# EEZ_DIB_MCU_r2B1.net
KiCad netlist of a schematic drawn in EAGLE
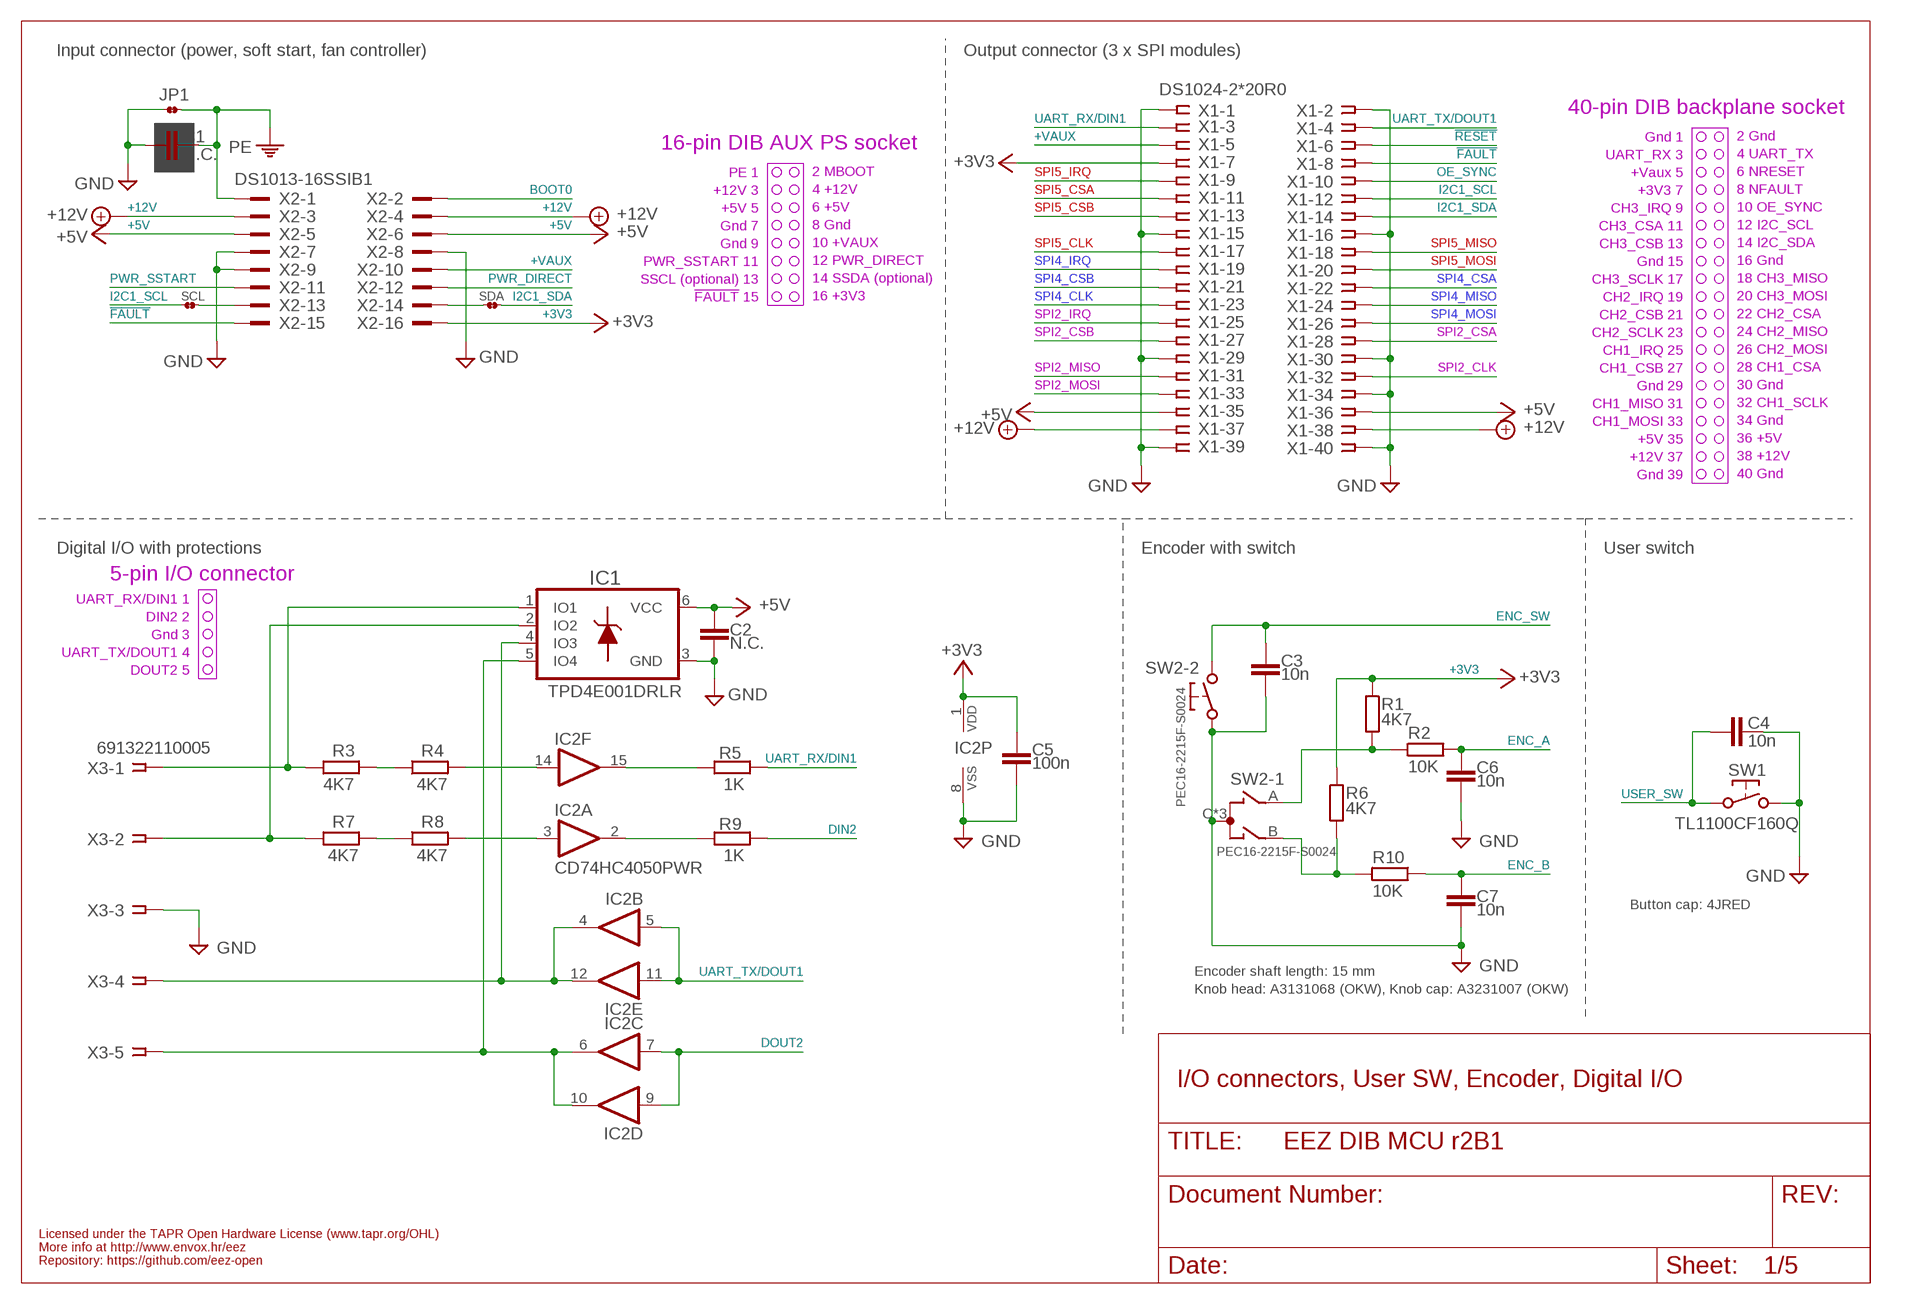
[diagram p0: schematic, sheet 1]
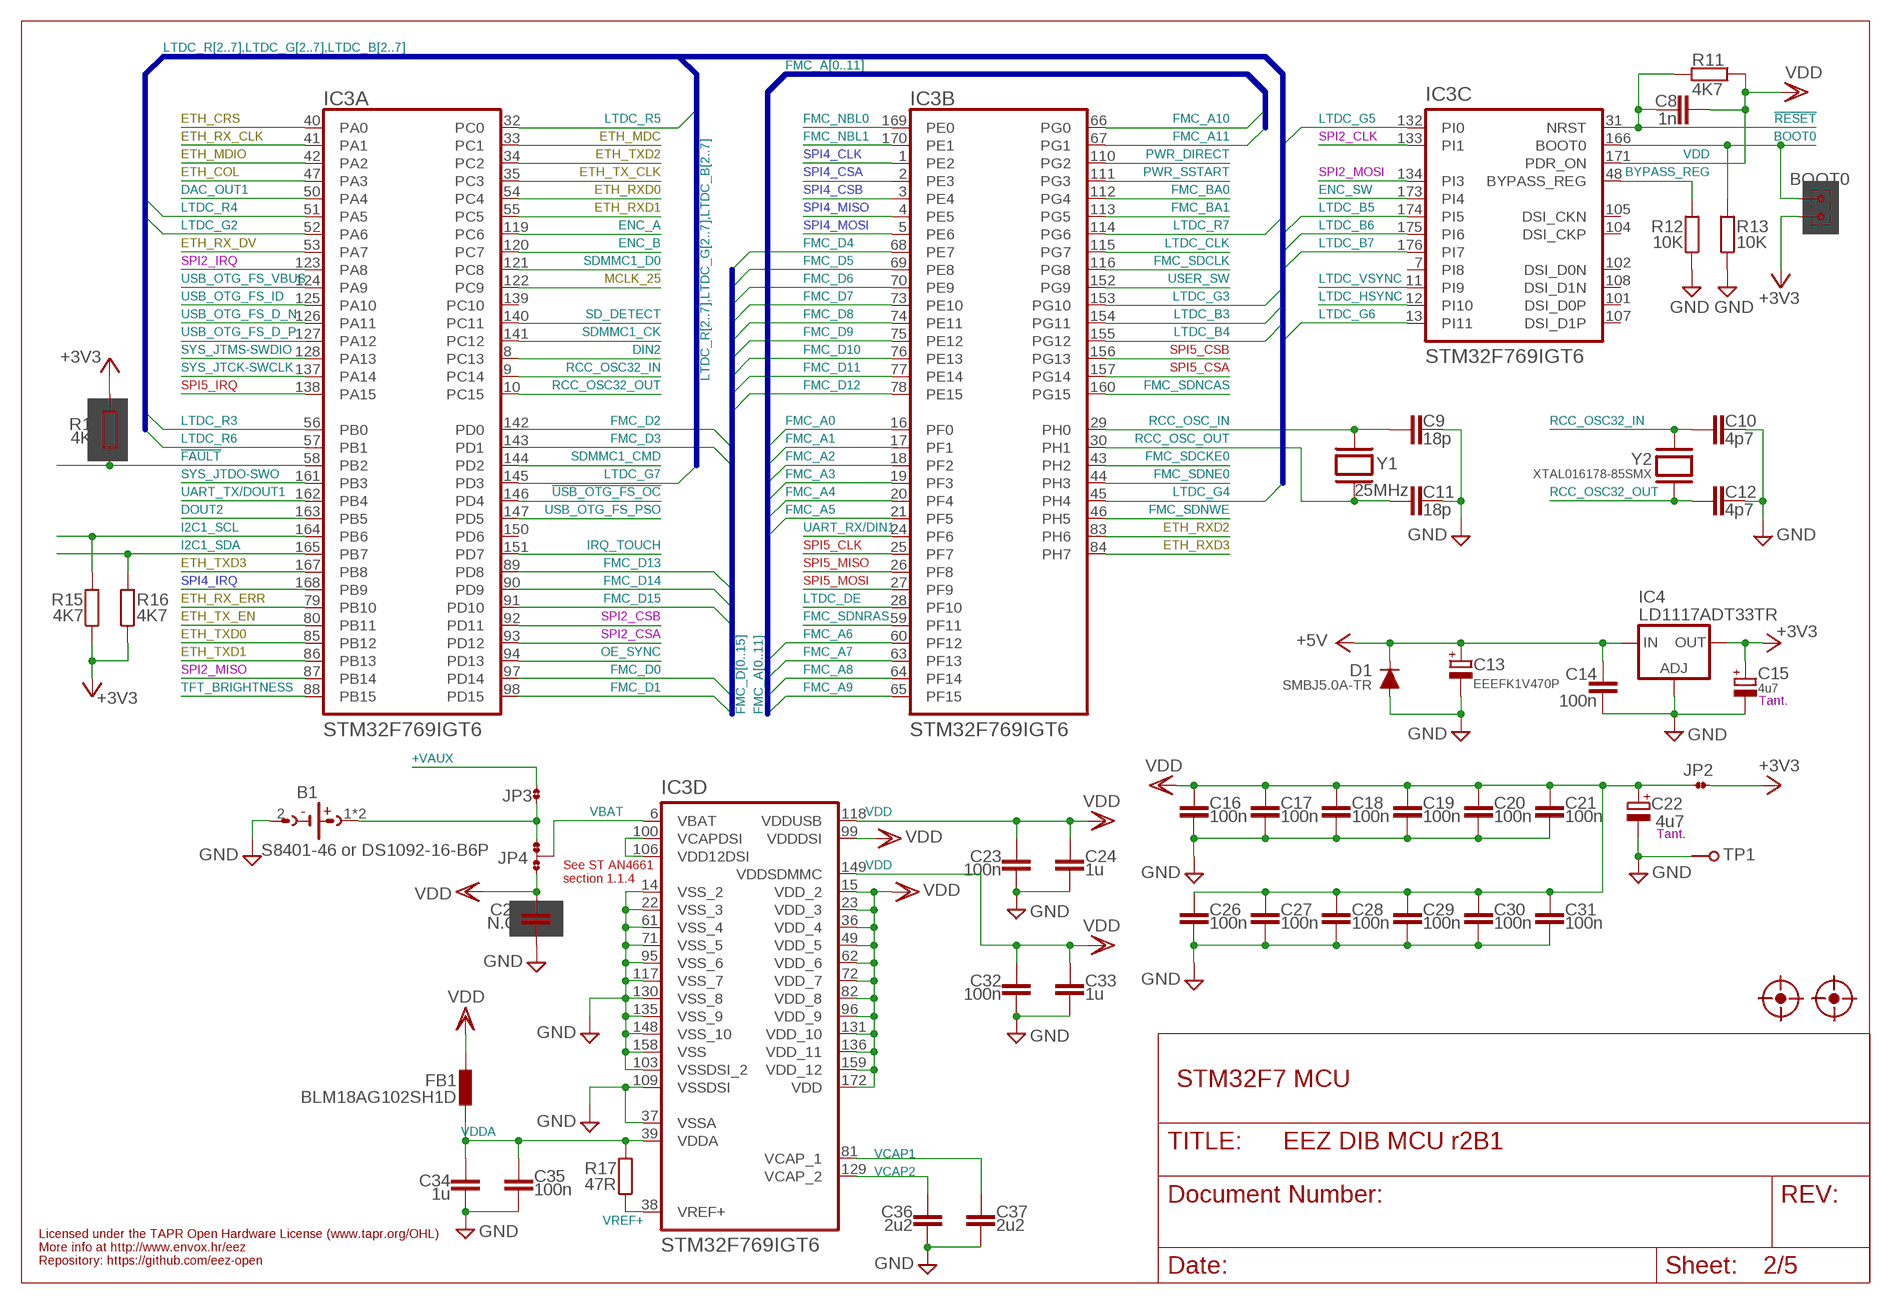
[diagram p1: schematic, sheet 2]
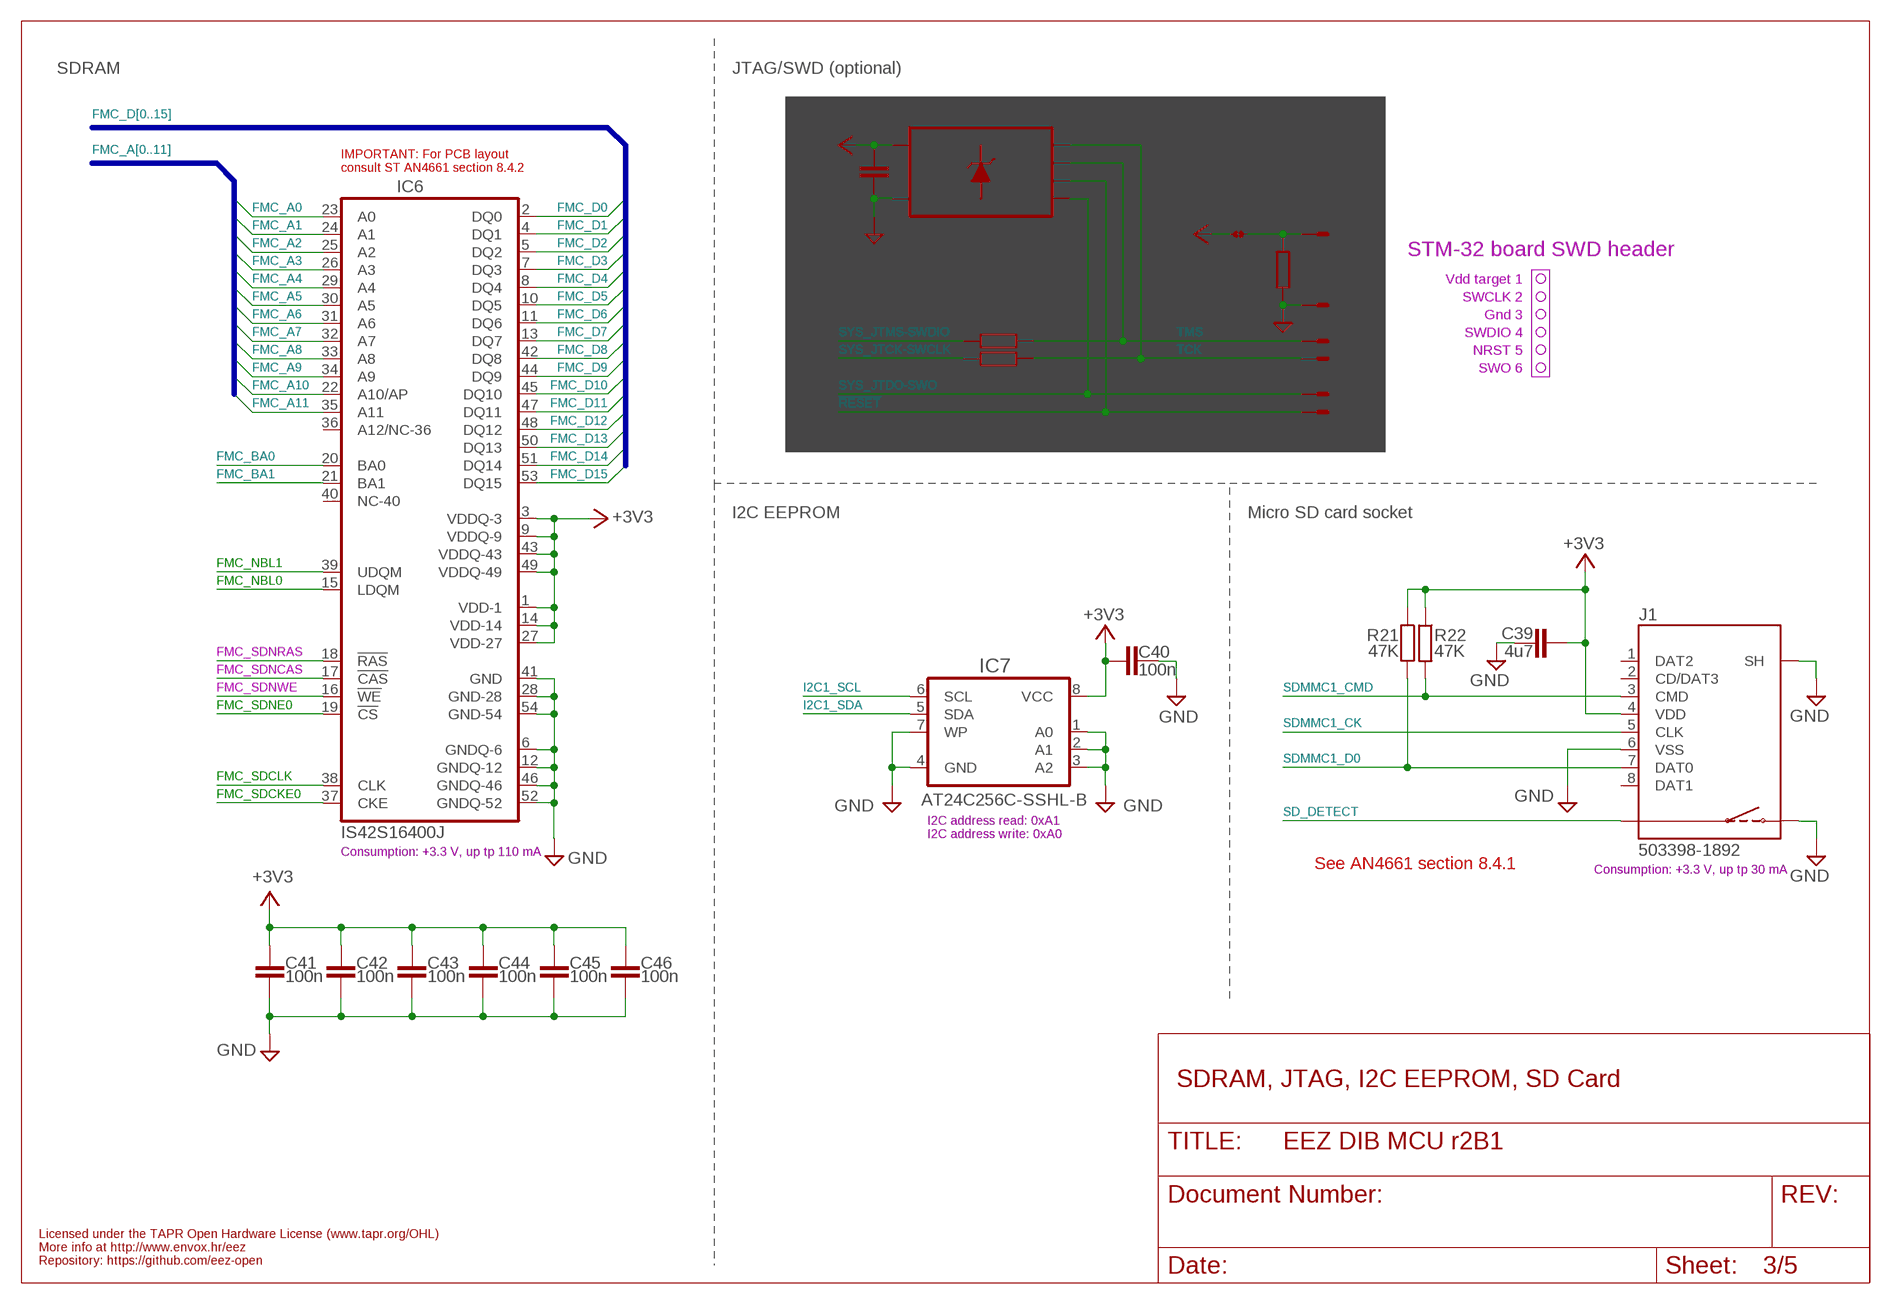
[diagram p2: schematic, sheet 3]
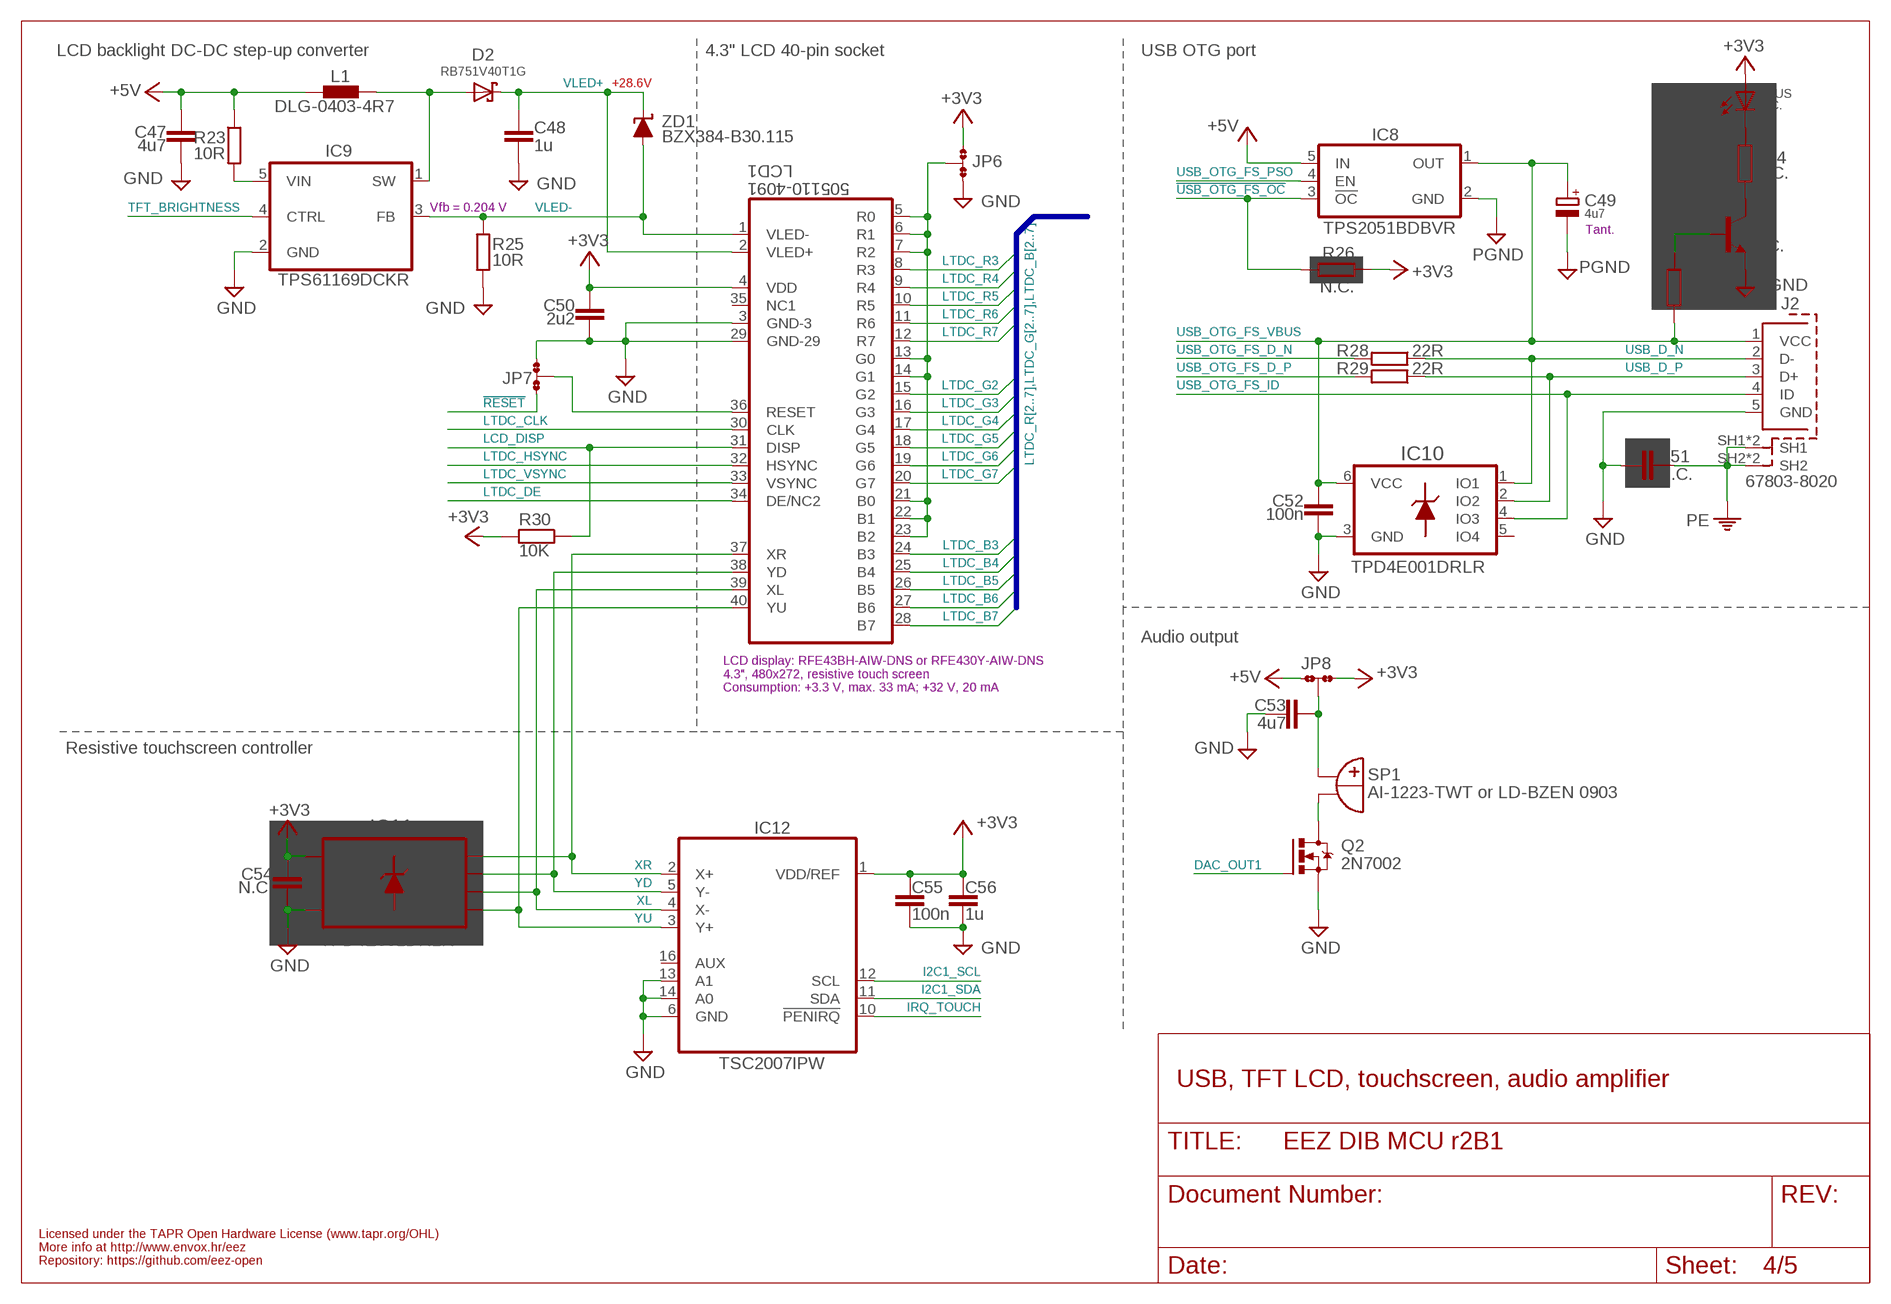
[diagram p3: schematic, sheet 4]
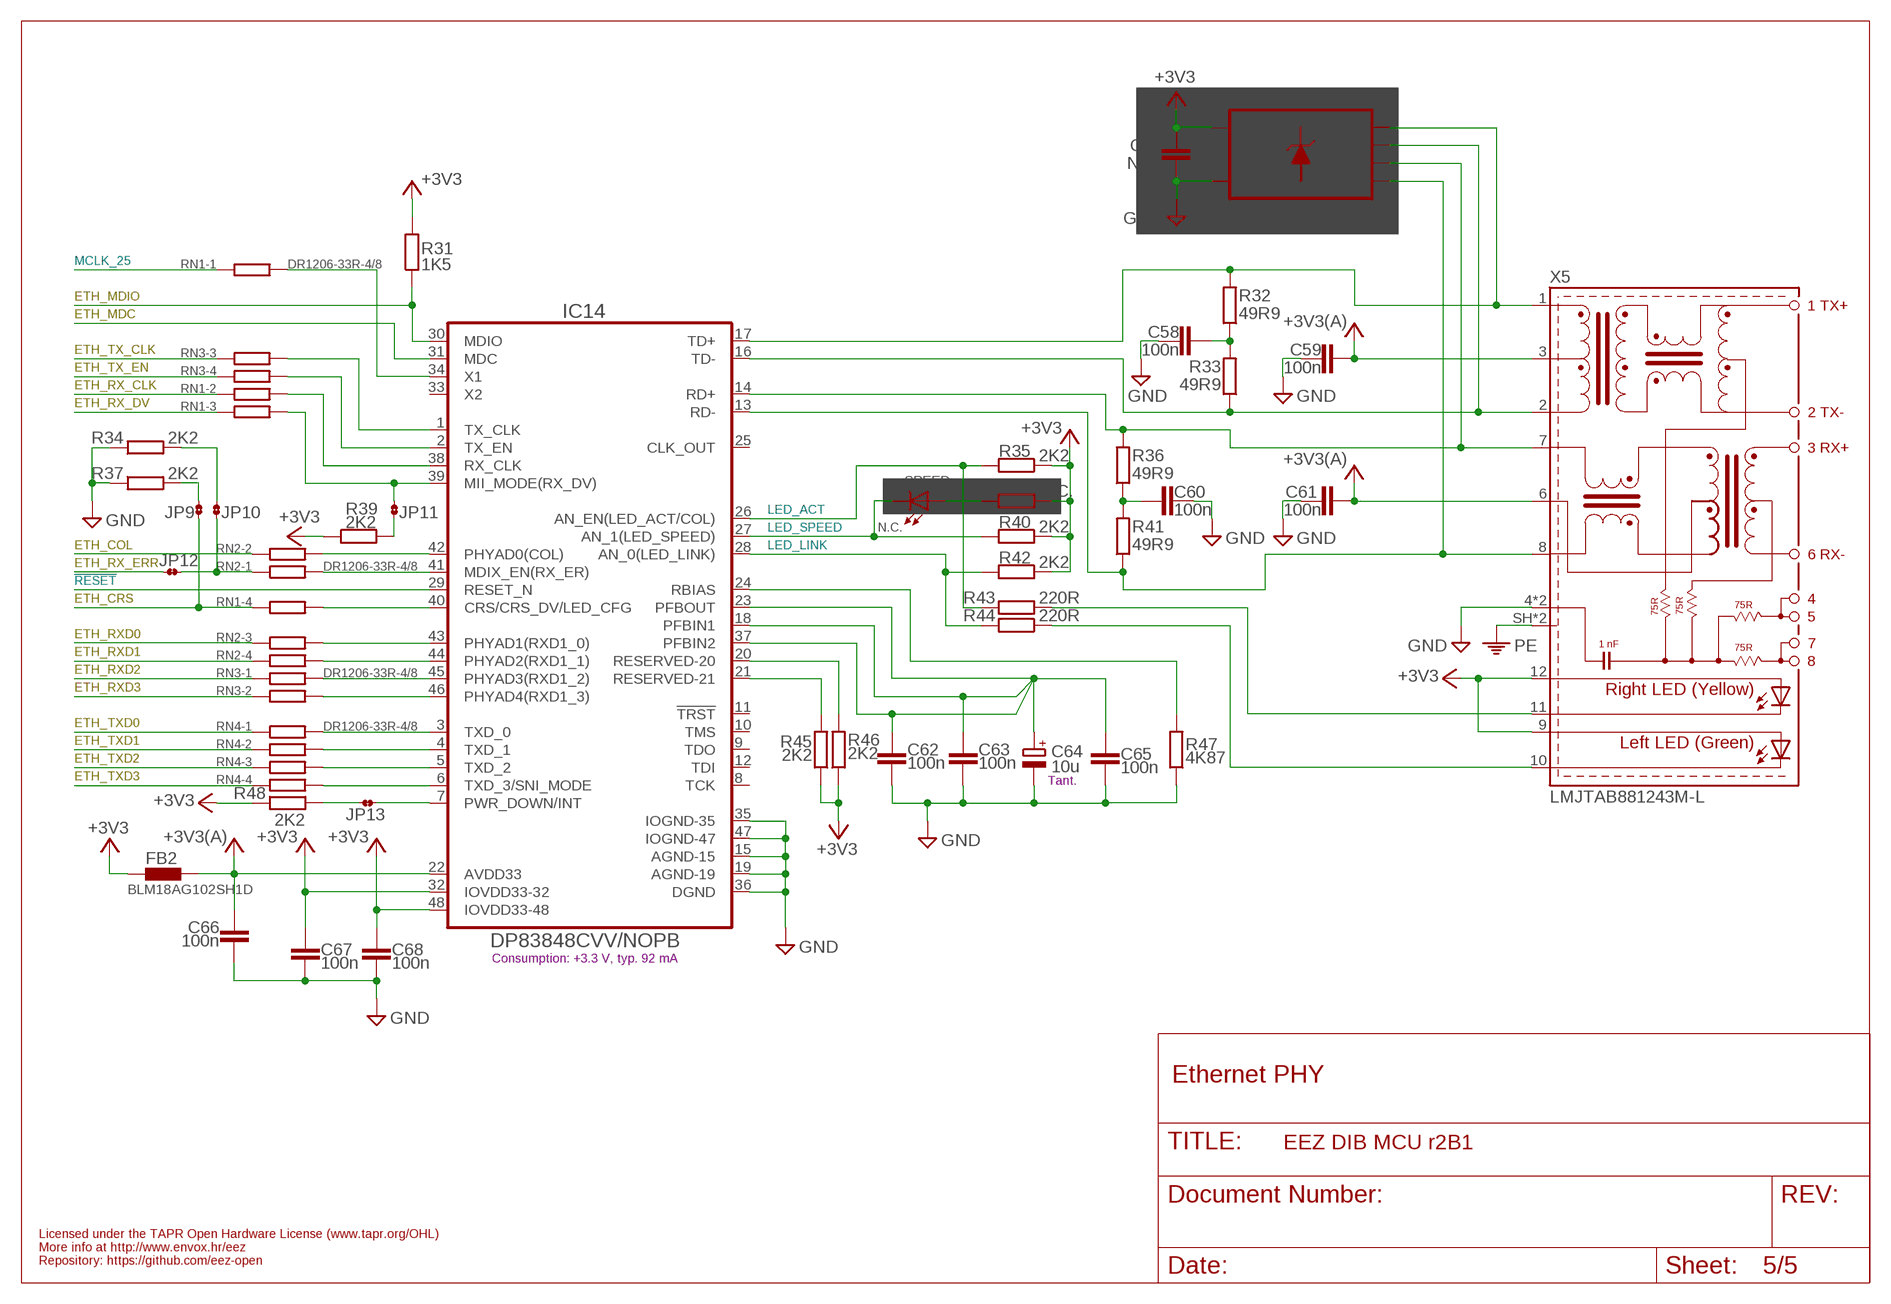
[diagram p4: schematic, sheet 5]

(export (version "E")
  (design (tool "Eeschema 10.0.6"))
  (components
    (comp (ref "C47")
      (value "4u7")
      (footprint "eagle-import:C1206")
      (libsource (lib "eagle-import") (part "C-EUC1206"))
    )
    (comp (ref "C48")
      (value "1u")
      (footprint "eagle-import:C0805")
      (libsource (lib "eagle-import") (part "C-EUC0805"))
    )
    (comp (ref "C49")
      (value "4u7")
      (footprint "eagle-import:EC1206")
      (libsource (lib "eagle-import") (part "ECAP1206"))
    )
    (comp (ref "C50")
      (value "2u2")
      (footprint "eagle-import:C0805")
      (libsource (lib "eagle-import") (part "C-EUC0805"))
    )
    (comp (ref "C51")
      (value "N.C.")
      (footprint "eagle-import:C0805")
      (libsource (lib "eagle-import") (part "C-EUC0805"))
    )
    (comp (ref "C52")
      (value "100n")
      (footprint "eagle-import:C0603")
      (libsource (lib "eagle-import") (part "C-EUC0603"))
    )
    (comp (ref "C53")
      (value "4u7")
      (footprint "eagle-import:C1206")
      (libsource (lib "eagle-import") (part "C-EUC1206"))
    )
    (comp (ref "C54")
      (value "N.C.")
      (footprint "eagle-import:C0603")
      (libsource (lib "eagle-import") (part "C-EUC0603"))
    )
    (comp (ref "C55")
      (value "100n")
      (footprint "eagle-import:C0603")
      (libsource (lib "eagle-import") (part "C-EUC0603"))
    )
    (comp (ref "C56")
      (value "1u")
      (footprint "eagle-import:C0805")
      (libsource (lib "eagle-import") (part "C-EUC0805"))
    )
    (comp (ref "D2")
      (value "RB751V40T1G")
      (footprint "eagle-import:SOD323-R")
      (libsource (lib "eagle-import") (part "SCHOTTKYSOD-323R"))
    )
    (comp (ref "IC8")
      (value "TPS2051BDBVR")
      (footprint "eagle-import:DBV5")
      (libsource (lib "eagle-import") (part "TPS2051B"))
    )
    (comp (ref "IC9")
      (value "TPS61169DCKR")
      (footprint "eagle-import:DCK5")
      (fields (field (name "MANUFACTURER") "Texas Instruments"))
      (libsource (lib "eagle-import") (part "TPS61169DCKR"))
    )
    (comp (ref "IC10")
      (value "TPD4E001DRLR")
      (footprint "eagle-import:DRL6")
      (libsource (lib "eagle-import") (part "TPD4E001-DRL"))
    )
    (comp (ref "IC11")
      (value "TPD4E001DRLR")
      (footprint "eagle-import:DRL6")
      (libsource (lib "eagle-import") (part "TPD4E001-DRL"))
    )
    (comp (ref "IC12")
      (value "TSC2007IPW")
      (footprint "eagle-import:PW(R-PDSO-G16)")
      (libsource (lib "eagle-import") (part "TSC2007IPW"))
    )
    (comp (ref "J2")
      (value "67803-8020")
      (footprint "eagle-import:678038020")
      (libsource (lib "eagle-import") (part "678038020"))
    )
    (comp (ref "JP6")
      (value "JP3-CUT")
      (footprint "eagle-import:JP3-CUT")
      (libsource (lib "eagle-import") (part "JP3-CUT"))
    )
    (comp (ref "JP7")
      (value "JP3-CUT")
      (footprint "eagle-import:JP3-CUT")
      (libsource (lib "eagle-import") (part "JP3-CUT"))
    )
    (comp (ref "JP8")
      (value "JP3-CUT")
      (footprint "eagle-import:JP3-CUT")
      (libsource (lib "eagle-import") (part "JP3-CUT"))
    )
    (comp (ref "L1")
      (value "DLG-0403-4R7")
      (footprint "eagle-import:DE0403")
      (libsource (lib "eagle-import") (part "DE0403"))
    )
    (comp (ref "LCD1")
      (value "505110-4091")
      (footprint "eagle-import:FPC_40")
      (libsource (lib "eagle-import") (part "RFE430Y-AIW-DNS"))
    )
    (comp (ref "Q1")
      (value "N.C.")
      (footprint "eagle-import:SOT23-BEC")
      (libsource (lib "eagle-import") (part "-NPN-SOT23-BECMMBT5551LT1"))
    )
    (comp (ref "Q2")
      (value "2N7002")
      (footprint "eagle-import:SOT103P240X110-3N")
      (fields (field (name "MPN") "2N7002-7-F"))
      (libsource (lib "eagle-import") (part "2N7002"))
    )
    (comp (ref "R23")
      (value "10R")
      (footprint "eagle-import:R0805")
      (libsource (lib "eagle-import") (part "R-EU_R0805"))
    )
    (comp (ref "R24")
      (value "N.C.")
      (footprint "eagle-import:R0805")
      (libsource (lib "eagle-import") (part "R-EU_R0805"))
    )
    (comp (ref "R25")
      (value "10R")
      (footprint "eagle-import:R0805")
      (libsource (lib "eagle-import") (part "R-EU_R0805"))
    )
    (comp (ref "R26")
      (value "N.C.")
      (footprint "eagle-import:R0805")
      (libsource (lib "eagle-import") (part "R-EU_R0805"))
    )
    (comp (ref "R27")
      (value "N.C.")
      (footprint "eagle-import:R0805")
      (libsource (lib "eagle-import") (part "R-EU_R0805"))
    )
    (comp (ref "R28")
      (value "22R")
      (footprint "eagle-import:R0805")
      (libsource (lib "eagle-import") (part "R-EU_R0805"))
    )
    (comp (ref "R29")
      (value "22R")
      (footprint "eagle-import:R0805")
      (libsource (lib "eagle-import") (part "R-EU_R0805"))
    )
    (comp (ref "R30")
      (value "10K")
      (footprint "eagle-import:R0805")
      (libsource (lib "eagle-import") (part "R-EU_R0805"))
    )
    (comp (ref "SP1")
      (value "AI-1223-TWT or LD-BZEN 0903")
      (footprint "eagle-import:AI-1223-TWT_COMBO")
      (libsource (lib "eagle-import") (part "AI-1223-TWT-LDB0903"))
    )
    (comp (ref "VBUS")
      (value "N.C.")
      (footprint "eagle-import:LED_0805")
      (libsource (lib "eagle-import") (part "LED0805"))
    )
    (comp (ref "ZD1")
      (value "BZX384-B30.115")
      (footprint "eagle-import:SOD323-W")
      (libsource (lib "eagle-import") (part "ZENER-DIODESOD323"))
    )
    (comp (ref "B1")
      (value "S8401-46 or DS1092-16-B6P")
      (footprint "eagle-import:S8401-46")
      (libsource (lib "eagle-import") (part "CELL_BATTERYVERT"))
    )
    (comp (ref "BOOT0")
      (value "JUMPER-2PIN-2MM")
      (footprint "eagle-import:2MM-2")
      (libsource (lib "eagle-import") (part "JUMPER-2PIN-2MM"))
    )
    (comp (ref "C8")
      (value "1n")
      (footprint "eagle-import:C0805")
      (libsource (lib "eagle-import") (part "C-EUC0805"))
    )
    (comp (ref "C9")
      (value "18p")
      (footprint "eagle-import:C0603")
      (libsource (lib "eagle-import") (part "C-EUC0603"))
    )
    (comp (ref "C10")
      (value "4p7")
      (footprint "eagle-import:C0603")
      (libsource (lib "eagle-import") (part "C-EUC0603"))
    )
    (comp (ref "C11")
      (value "18p")
      (footprint "eagle-import:C0603")
      (libsource (lib "eagle-import") (part "C-EUC0603"))
    )
    (comp (ref "C12")
      (value "4p7")
      (footprint "eagle-import:C0603")
      (libsource (lib "eagle-import") (part "C-EUC0603"))
    )
    (comp (ref "C13")
      (value "EEEFK1V470P")
      (footprint "eagle-import:CAPAE660X610N")
      (libsource (lib "eagle-import") (part "ECAPPANASONIC_H"))
    )
    (comp (ref "C14")
      (value "100n")
      (footprint "eagle-import:C0603")
      (libsource (lib "eagle-import") (part "C-EUC0603"))
    )
    (comp (ref "C15")
      (value "4u7")
      (footprint "eagle-import:EC1206")
      (libsource (lib "eagle-import") (part "ECAP1206"))
    )
    (comp (ref "C16")
      (value "100n")
      (footprint "eagle-import:C0603")
      (libsource (lib "eagle-import") (part "C-EUC0603"))
    )
    (comp (ref "C17")
      (value "100n")
      (footprint "eagle-import:C0603")
      (libsource (lib "eagle-import") (part "C-EUC0603"))
    )
    (comp (ref "C18")
      (value "100n")
      (footprint "eagle-import:C0603")
      (libsource (lib "eagle-import") (part "C-EUC0603"))
    )
    (comp (ref "C19")
      (value "100n")
      (footprint "eagle-import:C0603")
      (libsource (lib "eagle-import") (part "C-EUC0603"))
    )
    (comp (ref "C20")
      (value "100n")
      (footprint "eagle-import:C0603")
      (libsource (lib "eagle-import") (part "C-EUC0603"))
    )
    (comp (ref "C21")
      (value "100n")
      (footprint "eagle-import:C0603")
      (libsource (lib "eagle-import") (part "C-EUC0603"))
    )
    (comp (ref "C22")
      (value "4u7")
      (footprint "eagle-import:EC1206")
      (libsource (lib "eagle-import") (part "ECAP1206"))
    )
    (comp (ref "C23")
      (value "100n")
      (footprint "eagle-import:C0603")
      (libsource (lib "eagle-import") (part "C-EUC0603"))
    )
    (comp (ref "C24")
      (value "1u")
      (footprint "eagle-import:C0805")
      (libsource (lib "eagle-import") (part "C-EUC0805"))
    )
    (comp (ref "C25")
      (value "N.C.")
      (footprint "eagle-import:C0603")
      (libsource (lib "eagle-import") (part "C-EUC0603"))
    )
    (comp (ref "C26")
      (value "100n")
      (footprint "eagle-import:C0603")
      (libsource (lib "eagle-import") (part "C-EUC0603"))
    )
    (comp (ref "C27")
      (value "100n")
      (footprint "eagle-import:C0603")
      (libsource (lib "eagle-import") (part "C-EUC0603"))
    )
    (comp (ref "C28")
      (value "100n")
      (footprint "eagle-import:C0603")
      (libsource (lib "eagle-import") (part "C-EUC0603"))
    )
    (comp (ref "C29")
      (value "100n")
      (footprint "eagle-import:C0603")
      (libsource (lib "eagle-import") (part "C-EUC0603"))
    )
    (comp (ref "C30")
      (value "100n")
      (footprint "eagle-import:C0603")
      (libsource (lib "eagle-import") (part "C-EUC0603"))
    )
    (comp (ref "C31")
      (value "100n")
      (footprint "eagle-import:C0603")
      (libsource (lib "eagle-import") (part "C-EUC0603"))
    )
    (comp (ref "C32")
      (value "100n")
      (footprint "eagle-import:C0603")
      (libsource (lib "eagle-import") (part "C-EUC0603"))
    )
    (comp (ref "C33")
      (value "1u")
      (footprint "eagle-import:C0805")
      (libsource (lib "eagle-import") (part "C-EUC0805"))
    )
    (comp (ref "C34")
      (value "1u")
      (footprint "eagle-import:C0805")
      (libsource (lib "eagle-import") (part "C-EUC0805"))
    )
    (comp (ref "C35")
      (value "100n")
      (footprint "eagle-import:C0603")
      (libsource (lib "eagle-import") (part "C-EUC0603"))
    )
    (comp (ref "C36")
      (value "2u2")
      (footprint "eagle-import:C0805")
      (libsource (lib "eagle-import") (part "C-EUC0805"))
    )
    (comp (ref "C37")
      (value "2u2")
      (footprint "eagle-import:C0805")
      (libsource (lib "eagle-import") (part "C-EUC0805"))
    )
    (comp (ref "D1")
      (value "SMBJ5.0A-TR")
      (footprint "eagle-import:DO214AA")
      (libsource (lib "eagle-import") (part "DIODEDO214AA"))
    )
    (comp (ref "FB1")
      (value "BLM18AG102SH1D")
      (footprint "eagle-import:BEAD0603")
      (libsource (lib "eagle-import") (part "FERRITE_BEAD0603"))
    )
    (comp (ref "FM1")
      (value "FIDUCIAL")
      (footprint "eagle-import:FIDUCIAL")
      (libsource (lib "eagle-import") (part "FIDUCIAL"))
    )
    (comp (ref "FM2")
      (value "FIDUCIAL")
      (footprint "eagle-import:FIDUCIAL")
      (libsource (lib "eagle-import") (part "FIDUCIAL"))
    )
    (comp (ref "IC3")
      (value "STM32F769IGT6")
      (footprint "eagle-import:LQFP-176_24X24MM")
      (fields
        (field (name "MANUFACTURER_PART_NUMBER") "stm32f769ixt")
        (field (name "COPYRIGHT") "Copyright C 2016 Accelerated Designs. All rights reserved")
      )
      (libsource (lib "eagle-import") (part "STM32F769IXT"))
    )
    (comp (ref "IC4")
      (value "LD1117ADT33TR")
      (footprint "eagle-import:DPACK")
      (libsource (lib "eagle-import") (part "LD117A?DT33TR"))
    )
    (comp (ref "JP2")
      (value "JP2-NOCUT")
      (footprint "eagle-import:JP2-NOCUT")
      (libsource (lib "eagle-import") (part "JP2-NOCUT"))
    )
    (comp (ref "JP3")
      (value "JP2-CUT")
      (footprint "eagle-import:JP2-CUT")
      (libsource (lib "eagle-import") (part "JP2-CUT"))
    )
    (comp (ref "JP4")
      (value "JP3-CUT")
      (footprint "eagle-import:JP3-CUT")
      (libsource (lib "eagle-import") (part "JP3-CUT"))
    )
    (comp (ref "R11")
      (value "4K7")
      (footprint "eagle-import:R0805")
      (libsource (lib "eagle-import") (part "R-EU_R0805"))
    )
    (comp (ref "R12")
      (value "10K")
      (footprint "eagle-import:R0805")
      (libsource (lib "eagle-import") (part "R-EU_R0805"))
    )
    (comp (ref "R13")
      (value "10K")
      (footprint "eagle-import:R0805")
      (libsource (lib "eagle-import") (part "R-EU_R0805"))
    )
    (comp (ref "R14")
      (value "4K7")
      (footprint "eagle-import:R0805")
      (libsource (lib "eagle-import") (part "R-EU_R0805"))
    )
    (comp (ref "R15")
      (value "4K7")
      (footprint "eagle-import:R0805")
      (libsource (lib "eagle-import") (part "R-EU_R0805"))
    )
    (comp (ref "R16")
      (value "4K7")
      (footprint "eagle-import:R0805")
      (libsource (lib "eagle-import") (part "R-EU_R0805"))
    )
    (comp (ref "R17")
      (value "47R")
      (footprint "eagle-import:R0805")
      (libsource (lib "eagle-import") (part "R-EU_R0805"))
    )
    (comp (ref "TP1")
      (value "PCB_TEST_TABSHIELD")
      (footprint "eagle-import:PCB_SHIELD_TAB")
      (libsource (lib "eagle-import") (part "PCB_TEST_TABSHIELD"))
    )
    (comp (ref "Y1")
      (value "25MHz")
      (footprint "eagle-import:HC-49_4H")
      (libsource (lib "eagle-import") (part "XTALSMD"))
    )
    (comp (ref "Y2")
      (value "XTAL016178-85SMX")
      (footprint "eagle-import:85SMX")
      (libsource (lib "eagle-import") (part "XTAL85SMX"))
    )
    (comp (ref "C1")
      (value "N.C.")
      (footprint "eagle-import:C0805")
      (libsource (lib "eagle-import") (part "C-EUC0805"))
    )
    (comp (ref "C2")
      (value "N.C.")
      (footprint "eagle-import:C0603")
      (libsource (lib "eagle-import") (part "C-EUC0603"))
    )
    (comp (ref "C3")
      (value "10n")
      (footprint "eagle-import:C0805")
      (libsource (lib "eagle-import") (part "C-EUC0805"))
    )
    (comp (ref "C4")
      (value "10n")
      (footprint "eagle-import:C0805")
      (libsource (lib "eagle-import") (part "C-EUC0805"))
    )
    (comp (ref "C5")
      (value "100n")
      (footprint "eagle-import:C0603")
      (libsource (lib "eagle-import") (part "C-EUC0603"))
    )
    (comp (ref "C6")
      (value "10n")
      (footprint "eagle-import:C0805")
      (libsource (lib "eagle-import") (part "C-EUC0805"))
    )
    (comp (ref "C7")
      (value "10n")
      (footprint "eagle-import:C0805")
      (libsource (lib "eagle-import") (part "C-EUC0805"))
    )
    (comp (ref "IC1")
      (value "TPD4E001DRLR")
      (footprint "eagle-import:DRL6")
      (libsource (lib "eagle-import") (part "TPD4E001-DRL"))
    )
    (comp (ref "IC2")
      (value "CD74HC4050PWR")
      (footprint "eagle-import:PW16")
      (libsource (lib "eagle-import") (part "CD74HC4050PWR"))
    )
    (comp (ref "JP1")
      (value "JP2-NOCUT")
      (footprint "eagle-import:JP2-NOCUT")
      (libsource (lib "eagle-import") (part "JP2-NOCUT"))
    )
    (comp (ref "R1")
      (value "4K7")
      (footprint "eagle-import:R0805")
      (libsource (lib "eagle-import") (part "R-EU_R0805"))
    )
    (comp (ref "R2")
      (value "10K")
      (footprint "eagle-import:R0805")
      (libsource (lib "eagle-import") (part "R-EU_R0805"))
    )
    (comp (ref "R3")
      (value "4K7")
      (footprint "eagle-import:R0805")
      (libsource (lib "eagle-import") (part "R-EU_R0805"))
    )
    (comp (ref "R4")
      (value "4K7")
      (footprint "eagle-import:R0805")
      (libsource (lib "eagle-import") (part "R-EU_R0805"))
    )
    (comp (ref "R5")
      (value "1K")
      (footprint "eagle-import:R0805")
      (libsource (lib "eagle-import") (part "R-EU_R0805"))
    )
    (comp (ref "R6")
      (value "4K7")
      (footprint "eagle-import:R0805")
      (libsource (lib "eagle-import") (part "R-EU_R0805"))
    )
    (comp (ref "R7")
      (value "4K7")
      (footprint "eagle-import:R0805")
      (libsource (lib "eagle-import") (part "R-EU_R0805"))
    )
    (comp (ref "R8")
      (value "4K7")
      (footprint "eagle-import:R0805")
      (libsource (lib "eagle-import") (part "R-EU_R0805"))
    )
    (comp (ref "R9")
      (value "1K")
      (footprint "eagle-import:R0805")
      (libsource (lib "eagle-import") (part "R-EU_R0805"))
    )
    (comp (ref "R10")
      (value "10K")
      (footprint "eagle-import:R0805")
      (libsource (lib "eagle-import") (part "R-EU_R0805"))
    )
    (comp (ref "SCL")
      (value "JP2-NOCUT")
      (footprint "eagle-import:JP2-NOCUT")
      (libsource (lib "eagle-import") (part "JP2-NOCUT"))
    )
    (comp (ref "SDA")
      (value "JP2-NOCUT")
      (footprint "eagle-import:JP2-NOCUT")
      (libsource (lib "eagle-import") (part "JP2-NOCUT"))
    )
    (comp (ref "SW1")
      (value "TL1100CF160Q")
      (footprint "eagle-import:TL1100C")
      (libsource (lib "eagle-import") (part "TL1100C"))
    )
    (comp (ref "SW2")
      (value "PEC16-2215F-S0024")
      (footprint "eagle-import:PEC16-2215F")
      (libsource (lib "eagle-import") (part "ENCODER_SW-PEC16"))
    )
    (comp (ref "X1")
      (value "DS1024-2*20R0")
      (footprint "eagle-import:ZL263-40DG")
      (libsource (lib "eagle-import") (part "ZL263-40DG"))
    )
    (comp (ref "X2")
      (value "DS1013-16SSIB1")
      (footprint "eagle-import:IDC-16PIN")
      (libsource (lib "eagle-import") (part "IDC-16PIN"))
    )
    (comp (ref "X3")
      (value "691322110005")
      (footprint "eagle-import:MC1,5_5-G-3,5")
      (libsource (lib "eagle-import") (part "MC1,5/5-G-3,5"))
    )
    (comp (ref "C57")
      (value "N.C.")
      (footprint "eagle-import:C0603")
      (libsource (lib "eagle-import") (part "C-EUC0603"))
    )
    (comp (ref "C58")
      (value "100n")
      (footprint "eagle-import:C0603")
      (libsource (lib "eagle-import") (part "C-EUC0603"))
    )
    (comp (ref "C59")
      (value "100n")
      (footprint "eagle-import:C0603")
      (libsource (lib "eagle-import") (part "C-EUC0603"))
    )
    (comp (ref "C60")
      (value "100n")
      (footprint "eagle-import:C0603")
      (libsource (lib "eagle-import") (part "C-EUC0603"))
    )
    (comp (ref "C61")
      (value "100n")
      (footprint "eagle-import:C0603")
      (libsource (lib "eagle-import") (part "C-EUC0603"))
    )
    (comp (ref "C62")
      (value "100n")
      (footprint "eagle-import:C0603")
      (libsource (lib "eagle-import") (part "C-EUC0603"))
    )
    (comp (ref "C63")
      (value "100n")
      (footprint "eagle-import:C0603")
      (libsource (lib "eagle-import") (part "C-EUC0603"))
    )
    (comp (ref "C64")
      (value "10u")
      (footprint "eagle-import:EC1206")
      (libsource (lib "eagle-import") (part "ECAP1206"))
    )
    (comp (ref "C65")
      (value "100n")
      (footprint "eagle-import:C0603")
      (libsource (lib "eagle-import") (part "C-EUC0603"))
    )
    (comp (ref "C66")
      (value "100n")
      (footprint "eagle-import:C0603")
      (libsource (lib "eagle-import") (part "C-EUC0603"))
    )
    (comp (ref "C67")
      (value "100n")
      (footprint "eagle-import:C0603")
      (libsource (lib "eagle-import") (part "C-EUC0603"))
    )
    (comp (ref "C68")
      (value "100n")
      (footprint "eagle-import:C0603")
      (libsource (lib "eagle-import") (part "C-EUC0603"))
    )
    (comp (ref "FB2")
      (value "BLM18AG102SH1D")
      (footprint "eagle-import:BEAD0603")
      (libsource (lib "eagle-import") (part "FERRITE_BEAD0603"))
    )
    (comp (ref "IC13")
      (value "N.C.")
      (footprint "eagle-import:DRL6")
      (libsource (lib "eagle-import") (part "TPD4E001-DRL"))
    )
    (comp (ref "IC14")
      (value "DP83848CVV/NOPB")
      (footprint "eagle-import:PT48")
      (libsource (lib "eagle-import") (part "DP83848CVV/NOPB"))
    )
    (comp (ref "JP9")
      (value "JP2-CUT")
      (footprint "eagle-import:JP2-CUT")
      (libsource (lib "eagle-import") (part "JP2-CUT"))
    )
    (comp (ref "JP10")
      (value "JP2-CUT")
      (footprint "eagle-import:JP2-CUT")
      (libsource (lib "eagle-import") (part "JP2-CUT"))
    )
    (comp (ref "JP11")
      (value "JP2-CUT")
      (footprint "eagle-import:JP2-CUT")
      (libsource (lib "eagle-import") (part "JP2-CUT"))
    )
    (comp (ref "JP12")
      (value "JP2-NOCUT")
      (footprint "eagle-import:JP2-NOCUT")
      (libsource (lib "eagle-import") (part "JP2-NOCUT"))
    )
    (comp (ref "JP13")
      (value "JP2-NOCUT")
      (footprint "eagle-import:JP2-NOCUT")
      (libsource (lib "eagle-import") (part "JP2-NOCUT"))
    )
    (comp (ref "R31")
      (value "1K5")
      (footprint "eagle-import:R0805")
      (libsource (lib "eagle-import") (part "R-EU_R0805"))
    )
    (comp (ref "R32")
      (value "49R9")
      (footprint "eagle-import:R0805")
      (libsource (lib "eagle-import") (part "R-EU_R0805"))
    )
    (comp (ref "R33")
      (value "49R9")
      (footprint "eagle-import:R0805")
      (libsource (lib "eagle-import") (part "R-EU_R0805"))
    )
    (comp (ref "R34")
      (value "2K2")
      (footprint "eagle-import:R0805")
      (libsource (lib "eagle-import") (part "R-EU_R0805"))
    )
    (comp (ref "R35")
      (value "2K2")
      (footprint "eagle-import:R0805")
      (libsource (lib "eagle-import") (part "R-EU_R0805"))
    )
    (comp (ref "R36")
      (value "49R9")
      (footprint "eagle-import:R0805")
      (libsource (lib "eagle-import") (part "R-EU_R0805"))
    )
    (comp (ref "R37")
      (value "2K2")
      (footprint "eagle-import:R0805")
      (libsource (lib "eagle-import") (part "R-EU_R0805"))
    )
    (comp (ref "R38")
      (value "N.C.")
      (footprint "eagle-import:R0805")
      (libsource (lib "eagle-import") (part "R-EU_R0805"))
    )
    (comp (ref "R39")
      (value "2K2")
      (footprint "eagle-import:R0805")
      (libsource (lib "eagle-import") (part "R-EU_R0805"))
    )
    (comp (ref "R40")
      (value "2K2")
      (footprint "eagle-import:R0805")
      (libsource (lib "eagle-import") (part "R-EU_R0805"))
    )
    (comp (ref "R41")
      (value "49R9")
      (footprint "eagle-import:R0805")
      (libsource (lib "eagle-import") (part "R-EU_R0805"))
    )
    (comp (ref "R42")
      (value "2K2")
      (footprint "eagle-import:R0805")
      (libsource (lib "eagle-import") (part "R-EU_R0805"))
    )
    (comp (ref "R43")
      (value "220R")
      (footprint "eagle-import:R0805")
      (libsource (lib "eagle-import") (part "R-EU_R0805"))
    )
    (comp (ref "R44")
      (value "220R")
      (footprint "eagle-import:R0805")
      (libsource (lib "eagle-import") (part "R-EU_R0805"))
    )
    (comp (ref "R45")
      (value "2K2")
      (footprint "eagle-import:R0805")
      (libsource (lib "eagle-import") (part "R-EU_R0805"))
    )
    (comp (ref "R46")
      (value "2K2")
      (footprint "eagle-import:R0805")
      (libsource (lib "eagle-import") (part "R-EU_R0805"))
    )
    (comp (ref "R47")
      (value "4K87")
      (footprint "eagle-import:R0805")
      (libsource (lib "eagle-import") (part "R-EU_R0805"))
    )
    (comp (ref "R48")
      (value "2K2")
      (footprint "eagle-import:R0805")
      (libsource (lib "eagle-import") (part "R-EU_R0805"))
    )
    (comp (ref "RN1")
      (value "DR1206-33R-4/8")
      (footprint "eagle-import:CAY16")
      (libsource (lib "eagle-import") (part "R_ARRAY4"))
    )
    (comp (ref "RN2")
      (value "DR1206-33R-4/8")
      (footprint "eagle-import:CAY16")
      (libsource (lib "eagle-import") (part "R_ARRAY4"))
    )
    (comp (ref "RN3")
      (value "DR1206-33R-4/8")
      (footprint "eagle-import:CAY16")
      (libsource (lib "eagle-import") (part "R_ARRAY4"))
    )
    (comp (ref "RN4")
      (value "DR1206-33R-4/8")
      (footprint "eagle-import:CAY16")
      (libsource (lib "eagle-import") (part "R_ARRAY4"))
    )
    (comp (ref "SPEED")
      (value "N.C.")
      (footprint "eagle-import:LED_0805")
      (libsource (lib "eagle-import") (part "LED0805"))
    )
    (comp (ref "X5")
      (value "LMJTAB881243M-L")
      (footprint "eagle-import:RJ45-TRAFO-LED")
      (libsource (lib "eagle-import") (part "RJ45-TRAFO-LED"))
    )
    (comp (ref "C38")
      (value "N.C.")
      (footprint "eagle-import:C0603")
      (libsource (lib "eagle-import") (part "C-EUC0603"))
    )
    (comp (ref "C39")
      (value "4u7")
      (footprint "eagle-import:C1206")
      (libsource (lib "eagle-import") (part "C-EUC1206"))
    )
    (comp (ref "C40")
      (value "100n")
      (footprint "eagle-import:C0603")
      (libsource (lib "eagle-import") (part "C-EUC0603"))
    )
    (comp (ref "C41")
      (value "100n")
      (footprint "eagle-import:C0603")
      (libsource (lib "eagle-import") (part "C-EUC0603"))
    )
    (comp (ref "C42")
      (value "100n")
      (footprint "eagle-import:C0603")
      (libsource (lib "eagle-import") (part "C-EUC0603"))
    )
    (comp (ref "C43")
      (value "100n")
      (footprint "eagle-import:C0603")
      (libsource (lib "eagle-import") (part "C-EUC0603"))
    )
    (comp (ref "C44")
      (value "100n")
      (footprint "eagle-import:C0603")
      (libsource (lib "eagle-import") (part "C-EUC0603"))
    )
    (comp (ref "C45")
      (value "100n")
      (footprint "eagle-import:C0603")
      (libsource (lib "eagle-import") (part "C-EUC0603"))
    )
    (comp (ref "C46")
      (value "100n")
      (footprint "eagle-import:C0603")
      (libsource (lib "eagle-import") (part "C-EUC0603"))
    )
    (comp (ref "IC5")
      (value "N.C.")
      (footprint "eagle-import:DRL6")
      (libsource (lib "eagle-import") (part "TPD4E001-DRL"))
    )
    (comp (ref "IC6")
      (value "IS42S16400J")
      (footprint "eagle-import:TSOPII-54")
      (libsource (lib "eagle-import") (part "IS42S16400"))
    )
    (comp (ref "IC7")
      (value "AT24C256C-SSHL-B")
      (footprint "eagle-import:SOIC127P600X173-8N")
      (libsource (lib "eagle-import") (part "AT24CXXSOIC8"))
    )
    (comp (ref "J1")
      (value "503398-1892")
      (footprint "eagle-import:5033981892")
      (libsource (lib "eagle-import") (part "5033981892"))
    )
    (comp (ref "JP5")
      (value "JP2-CUT")
      (footprint "eagle-import:JP2-CUT")
      (libsource (lib "eagle-import") (part "JP2-CUT"))
    )
    (comp (ref "R18")
      (value "N.C.")
      (footprint "eagle-import:R0805")
      (libsource (lib "eagle-import") (part "R-EU_R0805"))
    )
    (comp (ref "R19")
      (value "N.C.")
      (footprint "eagle-import:R0805")
      (libsource (lib "eagle-import") (part "R-EU_R0805"))
    )
    (comp (ref "R20")
      (value "N.C.")
      (footprint "eagle-import:R0805")
      (libsource (lib "eagle-import") (part "R-EU_R0805"))
    )
    (comp (ref "R21")
      (value "47K")
      (footprint "eagle-import:R0805")
      (libsource (lib "eagle-import") (part "R-EU_R0805"))
    )
    (comp (ref "R22")
      (value "47K")
      (footprint "eagle-import:R0805")
      (libsource (lib "eagle-import") (part "R-EU_R0805"))
    )
    (comp (ref "X4")
      (value "N.C.")
      (footprint "eagle-import:22-23-2061")
      (fields (field (name "MF") "MOLEX") (field (name "MPN") "22-23-2061"))
      (libsource (lib "eagle-import") (part "22-23-2061"))
    )
  )
  (nets
    (net (code "1") (name "+3V3") (class "Default")
      (node (ref "BOOT0") (pin "2") (pinfunction "2_2") (pintype "passive"))
      (node (ref "C15") (pin "+") (pinfunction "+_+") (pintype "passive"))
      (node (ref "C38") (pin "1") (pinfunction "1_1") (pintype "passive"))
      (node (ref "C39") (pin "1") (pinfunction "1_1") (pintype "passive"))
      (node (ref "C40") (pin "2") (pinfunction "2_2") (pintype "passive"))
      (node (ref "C41") (pin "1") (pinfunction "1_1") (pintype "passive"))
      (node (ref "C42") (pin "1") (pinfunction "1_1") (pintype "passive"))
      (node (ref "C43") (pin "1") (pinfunction "1_1") (pintype "passive"))
      (node (ref "C44") (pin "1") (pinfunction "1_1") (pintype "passive"))
      (node (ref "C45") (pin "1") (pinfunction "1_1") (pintype "passive"))
      (node (ref "C46") (pin "1") (pinfunction "1_1") (pintype "passive"))
      (node (ref "C5") (pin "1") (pinfunction "1_1") (pintype "passive"))
      (node (ref "C50") (pin "1") (pinfunction "1_1") (pintype "passive"))
      (node (ref "C54") (pin "2") (pinfunction "2_2") (pintype "passive"))
      (node (ref "C55") (pin "2") (pinfunction "2_2") (pintype "passive"))
      (node (ref "C56") (pin "2") (pinfunction "2_2") (pintype "passive"))
      (node (ref "C57") (pin "1") (pinfunction "1_1") (pintype "passive"))
      (node (ref "C67") (pin "1") (pinfunction "1_1") (pintype "passive"))
      (node (ref "C68") (pin "1") (pinfunction "1_1") (pintype "passive"))
      (node (ref "FB2") (pin "P$1") (pinfunction "1_P$1") (pintype "passive"))
      (node (ref "IC11") (pin "6") (pinfunction "VCC_6") (pintype "passive"))
      (node (ref "IC12") (pin "1") (pinfunction "VDD/REF_1") (pintype "passive"))
      (node (ref "IC13") (pin "6") (pinfunction "VCC_6") (pintype "passive"))
      (node (ref "IC14") (pin "32") (pinfunction "IOVDD33-32_32") (pintype "power_in"))
      (node (ref "IC14") (pin "48") (pinfunction "IOVDD33-48_48") (pintype "power_in"))
      (node (ref "IC2") (pin "1") (pinfunction "VDD_1") (pintype "power_in"))
      (node (ref "IC4") (pin "4") (pinfunction "OUT_4") (pintype "passive"))
      (node (ref "IC5") (pin "6") (pinfunction "VCC_6") (pintype "passive"))
      (node (ref "IC6") (pin "1") (pinfunction "VDD-1_1") (pintype "power_in"))
      (node (ref "IC6") (pin "14") (pinfunction "VDD-14_14") (pintype "power_in"))
      (node (ref "IC6") (pin "27") (pinfunction "VDD-27_27") (pintype "power_in"))
      (node (ref "IC6") (pin "3") (pinfunction "VDDQ-3_3") (pintype "power_in"))
      (node (ref "IC6") (pin "43") (pinfunction "VDDQ-43_43") (pintype "power_in"))
      (node (ref "IC6") (pin "49") (pinfunction "VDDQ-49_49") (pintype "power_in"))
      (node (ref "IC6") (pin "9") (pinfunction "VDDQ-9_9") (pintype "power_in"))
      (node (ref "IC7") (pin "8") (pinfunction "VCC_8") (pintype "power_in"))
      (node (ref "J1") (pin "4") (pinfunction "VDD_4") (pintype "power_in"))
      (node (ref "JP2") (pin "2") (pinfunction "2_2") (pintype "passive"))
      (node (ref "JP5") (pin "1") (pinfunction "1_1") (pintype "passive"))
      (node (ref "JP6") (pin "NO") (pinfunction "NO_NO") (pintype "passive"))
      (node (ref "JP8") (pin "NC") (pinfunction "NC_NC") (pintype "passive"))
      (node (ref "LCD1") (pin "4") (pinfunction "VDD_4") (pintype "power_in"))
      (node (ref "R1") (pin "1") (pinfunction "1_1") (pintype "passive"))
      (node (ref "R14") (pin "1") (pinfunction "1_1") (pintype "passive"))
      (node (ref "R15") (pin "1") (pinfunction "1_1") (pintype "passive"))
      (node (ref "R16") (pin "1") (pinfunction "1_1") (pintype "passive"))
      (node (ref "R21") (pin "1") (pinfunction "1_1") (pintype "passive"))
      (node (ref "R22") (pin "1") (pinfunction "1_1") (pintype "passive"))
      (node (ref "R26") (pin "2") (pinfunction "2_2") (pintype "passive"))
      (node (ref "R30") (pin "2") (pinfunction "2_2") (pintype "passive"))
      (node (ref "R31") (pin "2") (pinfunction "2_2") (pintype "passive"))
      (node (ref "R35") (pin "1") (pinfunction "1_1") (pintype "passive"))
      (node (ref "R38") (pin "1") (pinfunction "1_1") (pintype "passive"))
      (node (ref "R39") (pin "1") (pinfunction "1_1") (pintype "passive"))
      (node (ref "R40") (pin "1") (pinfunction "1_1") (pintype "passive"))
      (node (ref "R42") (pin "1") (pinfunction "1_1") (pintype "passive"))
      (node (ref "R45") (pin "1") (pinfunction "1_1") (pintype "passive"))
      (node (ref "R46") (pin "1") (pinfunction "1_1") (pintype "passive"))
      (node (ref "R48") (pin "1") (pinfunction "1_1") (pintype "passive"))
      (node (ref "R6") (pin "1") (pinfunction "1_1") (pintype "passive"))
      (node (ref "VBUS") (pin "A") (pinfunction "A_A") (pintype "passive"))
      (node (ref "X1") (pin "7") (pinfunction "1_7") (pintype "passive"))
      (node (ref "X2") (pin "16") (pinfunction "1_16") (pintype "passive"))
      (node (ref "X5") (pin "12") (pinfunction "YELLOW_A_12") (pintype "passive"))
      (node (ref "X5") (pin "9") (pinfunction "GREEN-A_9") (pintype "passive"))
    )
    (net (code "2") (name "+3V3(A)") (class "Default")
      (node (ref "C59") (pin "2") (pinfunction "2_2") (pintype "passive"))
      (node (ref "C61") (pin "2") (pinfunction "2_2") (pintype "passive"))
      (node (ref "C66") (pin "1") (pinfunction "1_1") (pintype "passive"))
      (node (ref "FB2") (pin "P$2") (pinfunction "2_P$2") (pintype "passive"))
      (node (ref "IC14") (pin "22") (pinfunction "AVDD33_22") (pintype "power_in"))
      (node (ref "X5") (pin "3") (pinfunction "CT_3") (pintype "input"))
      (node (ref "X5") (pin "6") (pinfunction "CR_6") (pintype "input"))
    )
    (net (code "3") (name "+5V") (class "Default")
      (node (ref "C13") (pin "1") (pinfunction "+_1") (pintype "passive"))
      (node (ref "C14") (pin "1") (pinfunction "1_1") (pintype "passive"))
      (node (ref "C2") (pin "1") (pinfunction "1_1") (pintype "passive"))
      (node (ref "C47") (pin "1") (pinfunction "1_1") (pintype "passive"))
      (node (ref "D1") (pin "C") (pinfunction "C_C") (pintype "passive"))
      (node (ref "IC1") (pin "6") (pinfunction "VCC_6") (pintype "passive"))
      (node (ref "IC4") (pin "3") (pinfunction "IN_3") (pintype "input"))
      (node (ref "IC8") (pin "5") (pinfunction "IN_5") (pintype "input"))
      (node (ref "JP8") (pin "NO") (pinfunction "NO_NO") (pintype "passive"))
      (node (ref "L1") (pin "1") (pinfunction "1_1") (pintype "passive"))
      (node (ref "R23") (pin "1") (pinfunction "1_1") (pintype "passive"))
      (node (ref "X1") (pin "35") (pinfunction "1_35") (pintype "passive"))
      (node (ref "X1") (pin "36") (pinfunction "1_36") (pintype "passive"))
      (node (ref "X2") (pin "5") (pinfunction "1_5") (pintype "passive"))
      (node (ref "X2") (pin "6") (pinfunction "1_6") (pintype "passive"))
    )
    (net (code "4") (name "+12V") (class "Default")
      (node (ref "X1") (pin "37") (pinfunction "1_37") (pintype "passive"))
      (node (ref "X1") (pin "38") (pinfunction "1_38") (pintype "passive"))
      (node (ref "X2") (pin "3") (pinfunction "1_3") (pintype "passive"))
      (node (ref "X2") (pin "4") (pinfunction "1_4") (pintype "passive"))
    )
    (net (code "5") (name "+VAUX") (class "Default")
      (node (ref "JP3") (pin "2") (pinfunction "2_2") (pintype "passive"))
      (node (ref "X1") (pin "5") (pinfunction "1_5") (pintype "passive"))
      (node (ref "X2") (pin "10") (pinfunction "1_10") (pintype "passive"))
    )
    (net (code "12") (name "BOOT0") (class "Default")
      (node (ref "BOOT0") (pin "1") (pinfunction "1_1") (pintype "passive"))
      (node (ref "IC3") (pin "166") (pinfunction "BOOT0_166") (pintype "input"))
      (node (ref "R13") (pin "2") (pinfunction "2_2") (pintype "passive"))
      (node (ref "X2") (pin "2") (pinfunction "1_2") (pintype "passive"))
    )
    (net (code "13") (name "BYPASS_REG") (class "Default")
      (node (ref "IC3") (pin "48") (pinfunction "BYPASS_REG_48") (pintype "input"))
      (node (ref "R12") (pin "2") (pinfunction "2_2") (pintype "passive"))
    )
    (net (code "14") (name "DAC_OUT1") (class "Default")
      (node (ref "IC3") (pin "50") (pinfunction "PA4_50") (pintype "bidirectional"))
      (node (ref "Q2") (pin "1") (pinfunction "G_1") (pintype "passive"))
    )
    (net (code "15") (name "DIN2") (class "Default")
      (node (ref "IC3") (pin "8") (pinfunction "PC13_8") (pintype "bidirectional"))
      (node (ref "R9") (pin "2") (pinfunction "2_2") (pintype "passive"))
    )
    (net (code "16") (name "DOUT2") (class "Default")
      (node (ref "IC2") (pin "7") (pinfunction "I_7") (pintype "input"))
      (node (ref "IC2") (pin "9") (pinfunction "I_9") (pintype "input"))
      (node (ref "IC3") (pin "163") (pinfunction "PB5_163") (pintype "bidirectional"))
    )
    (net (code "17") (name "ENC_A") (class "Default")
      (node (ref "C6") (pin "2") (pinfunction "2_2") (pintype "passive"))
      (node (ref "IC3") (pin "119") (pinfunction "PC6_119") (pintype "bidirectional"))
      (node (ref "R2") (pin "1") (pinfunction "1_1") (pintype "passive"))
    )
    (net (code "18") (name "ENC_B") (class "Default")
      (node (ref "C7") (pin "1") (pinfunction "1_1") (pintype "passive"))
      (node (ref "IC3") (pin "120") (pinfunction "PC7_120") (pintype "bidirectional"))
      (node (ref "R10") (pin "1") (pinfunction "1_1") (pintype "passive"))
    )
    (net (code "19") (name "ENC_SW") (class "Default")
      (node (ref "C3") (pin "2") (pinfunction "2_2") (pintype "passive"))
      (node (ref "IC3") (pin "173") (pinfunction "PI4_173") (pintype "bidirectional"))
      (node (ref "SW2") (pin "E") (pinfunction "2_E") (pintype "passive"))
    )
    (net (code "20") (name "ETH_COL") (class "Default")
      (node (ref "IC3") (pin "47") (pinfunction "PA3_47") (pintype "bidirectional"))
      (node (ref "RN2") (pin "2") (pinfunction "1_2") (pintype "passive"))
    )
    (net (code "21") (name "ETH_CRS") (class "Default")
      (node (ref "IC3") (pin "40") (pinfunction "PA0_40") (pintype "bidirectional"))
      (node (ref "JP9") (pin "1") (pinfunction "1_1") (pintype "passive"))
      (node (ref "RN1") (pin "4") (pinfunction "1_4") (pintype "passive"))
    )
    (net (code "22") (name "ETH_MDC") (class "Default")
      (node (ref "IC14") (pin "31") (pinfunction "MDC_31") (pintype "input"))
      (node (ref "IC3") (pin "33") (pinfunction "PC1_33") (pintype "bidirectional"))
    )
    (net (code "23") (name "ETH_MDIO") (class "Default")
      (node (ref "IC14") (pin "30") (pinfunction "MDIO_30") (pintype "bidirectional"))
      (node (ref "IC3") (pin "42") (pinfunction "PA2_42") (pintype "bidirectional"))
      (node (ref "R31") (pin "1") (pinfunction "1_1") (pintype "passive"))
    )
    (net (code "24") (name "ETH_RXD0") (class "Default")
      (node (ref "IC3") (pin "54") (pinfunction "PC4_54") (pintype "bidirectional"))
      (node (ref "RN2") (pin "3") (pinfunction "1_3") (pintype "passive"))
    )
    (net (code "25") (name "ETH_RXD1") (class "Default")
      (node (ref "IC3") (pin "55") (pinfunction "PC5_55") (pintype "bidirectional"))
      (node (ref "RN2") (pin "4") (pinfunction "1_4") (pintype "passive"))
    )
    (net (code "26") (name "ETH_RXD2") (class "Default")
      (node (ref "IC3") (pin "83") (pinfunction "PH6_83") (pintype "bidirectional"))
      (node (ref "RN3") (pin "1") (pinfunction "1_1") (pintype "passive"))
    )
    (net (code "27") (name "ETH_RXD3") (class "Default")
      (node (ref "IC3") (pin "84") (pinfunction "PH7_84") (pintype "bidirectional"))
      (node (ref "RN3") (pin "2") (pinfunction "1_2") (pintype "passive"))
    )
    (net (code "28") (name "ETH_RX_CLK") (class "Default")
      (node (ref "IC3") (pin "41") (pinfunction "PA1_41") (pintype "bidirectional"))
      (node (ref "RN1") (pin "2") (pinfunction "1_2") (pintype "passive"))
    )
    (net (code "29") (name "ETH_RX_DV") (class "Default")
      (node (ref "IC3") (pin "53") (pinfunction "PA7_53") (pintype "bidirectional"))
      (node (ref "RN1") (pin "3") (pinfunction "1_3") (pintype "passive"))
    )
    (net (code "30") (name "ETH_RX_ERR") (class "Default")
      (node (ref "IC3") (pin "79") (pinfunction "PB10_79") (pintype "bidirectional"))
      (node (ref "JP12") (pin "2") (pinfunction "2_2") (pintype "passive"))
    )
    (net (code "31") (name "ETH_TXD0") (class "Default")
      (node (ref "IC3") (pin "85") (pinfunction "PB12_85") (pintype "bidirectional"))
      (node (ref "RN4") (pin "1") (pinfunction "1_1") (pintype "passive"))
    )
    (net (code "32") (name "ETH_TXD1") (class "Default")
      (node (ref "IC3") (pin "86") (pinfunction "PB13_86") (pintype "bidirectional"))
      (node (ref "RN4") (pin "2") (pinfunction "1_2") (pintype "passive"))
    )
    (net (code "33") (name "ETH_TXD2") (class "Default")
      (node (ref "IC3") (pin "34") (pinfunction "PC2_34") (pintype "bidirectional"))
      (node (ref "RN4") (pin "3") (pinfunction "1_3") (pintype "passive"))
    )
    (net (code "34") (name "ETH_TXD3") (class "Default")
      (node (ref "IC3") (pin "167") (pinfunction "PB8_167") (pintype "bidirectional"))
      (node (ref "RN4") (pin "4") (pinfunction "1_4") (pintype "passive"))
    )
    (net (code "35") (name "ETH_TX_CLK") (class "Default")
      (node (ref "IC3") (pin "35") (pinfunction "PC3_35") (pintype "bidirectional"))
      (node (ref "RN3") (pin "3") (pinfunction "1_3") (pintype "passive"))
    )
    (net (code "36") (name "ETH_TX_EN") (class "Default")
      (node (ref "IC3") (pin "80") (pinfunction "PB11_80") (pintype "bidirectional"))
      (node (ref "RN3") (pin "4") (pinfunction "1_4") (pintype "passive"))
    )
    (net (code "37") (name "FMC_A0") (class "Default")
      (node (ref "IC3") (pin "16") (pinfunction "PF0_16") (pintype "bidirectional"))
      (node (ref "IC6") (pin "23") (pinfunction "A0_23") (pintype "input"))
    )
    (net (code "38") (name "FMC_A1") (class "Default")
      (node (ref "IC3") (pin "17") (pinfunction "PF1_17") (pintype "bidirectional"))
      (node (ref "IC6") (pin "24") (pinfunction "A1_24") (pintype "input"))
    )
    (net (code "39") (name "FMC_A2") (class "Default")
      (node (ref "IC3") (pin "18") (pinfunction "PF2_18") (pintype "bidirectional"))
      (node (ref "IC6") (pin "25") (pinfunction "A2_25") (pintype "input"))
    )
    (net (code "40") (name "FMC_A3") (class "Default")
      (node (ref "IC3") (pin "19") (pinfunction "PF3_19") (pintype "bidirectional"))
      (node (ref "IC6") (pin "26") (pinfunction "A3_26") (pintype "input"))
    )
    (net (code "41") (name "FMC_A4") (class "Default")
      (node (ref "IC3") (pin "20") (pinfunction "PF4_20") (pintype "bidirectional"))
      (node (ref "IC6") (pin "29") (pinfunction "A4_29") (pintype "input"))
    )
    (net (code "42") (name "FMC_A5") (class "Default")
      (node (ref "IC3") (pin "21") (pinfunction "PF5_21") (pintype "bidirectional"))
      (node (ref "IC6") (pin "30") (pinfunction "A5_30") (pintype "input"))
    )
    (net (code "43") (name "FMC_A6") (class "Default")
      (node (ref "IC3") (pin "60") (pinfunction "PF12_60") (pintype "bidirectional"))
      (node (ref "IC6") (pin "31") (pinfunction "A6_31") (pintype "input"))
    )
    (net (code "44") (name "FMC_A7") (class "Default")
      (node (ref "IC3") (pin "63") (pinfunction "PF13_63") (pintype "bidirectional"))
      (node (ref "IC6") (pin "32") (pinfunction "A7_32") (pintype "input"))
    )
    (net (code "45") (name "FMC_A8") (class "Default")
      (node (ref "IC3") (pin "64") (pinfunction "PF14_64") (pintype "bidirectional"))
      (node (ref "IC6") (pin "33") (pinfunction "A8_33") (pintype "input"))
    )
    (net (code "46") (name "FMC_A9") (class "Default")
      (node (ref "IC3") (pin "65") (pinfunction "PF15_65") (pintype "bidirectional"))
      (node (ref "IC6") (pin "34") (pinfunction "A9_34") (pintype "input"))
    )
    (net (code "47") (name "FMC_A10") (class "Default")
      (node (ref "IC3") (pin "66") (pinfunction "PG0_66") (pintype "bidirectional"))
      (node (ref "IC6") (pin "22") (pinfunction "A10/AP_22") (pintype "input"))
    )
    (net (code "48") (name "FMC_A11") (class "Default")
      (node (ref "IC3") (pin "67") (pinfunction "PG1_67") (pintype "bidirectional"))
      (node (ref "IC6") (pin "35") (pinfunction "A11_35") (pintype "input"))
    )
    (net (code "49") (name "FMC_BA0") (class "Default")
      (node (ref "IC3") (pin "112") (pinfunction "PG4_112") (pintype "bidirectional"))
      (node (ref "IC6") (pin "20") (pinfunction "BA0_20") (pintype "input"))
    )
    (net (code "50") (name "FMC_BA1") (class "Default")
      (node (ref "IC3") (pin "113") (pinfunction "PG5_113") (pintype "bidirectional"))
      (node (ref "IC6") (pin "21") (pinfunction "BA1_21") (pintype "input"))
    )
    (net (code "51") (name "FMC_D0") (class "Default")
      (node (ref "IC3") (pin "97") (pinfunction "PD14_97") (pintype "bidirectional"))
      (node (ref "IC6") (pin "2") (pinfunction "DQ0_2") (pintype "bidirectional"))
    )
    (net (code "52") (name "FMC_D1") (class "Default")
      (node (ref "IC3") (pin "98") (pinfunction "PD15_98") (pintype "bidirectional"))
      (node (ref "IC6") (pin "4") (pinfunction "DQ1_4") (pintype "bidirectional"))
    )
    (net (code "53") (name "FMC_D2") (class "Default")
      (node (ref "IC3") (pin "142") (pinfunction "PD0_142") (pintype "bidirectional"))
      (node (ref "IC6") (pin "5") (pinfunction "DQ2_5") (pintype "bidirectional"))
    )
    (net (code "54") (name "FMC_D3") (class "Default")
      (node (ref "IC3") (pin "143") (pinfunction "PD1_143") (pintype "bidirectional"))
      (node (ref "IC6") (pin "7") (pinfunction "DQ3_7") (pintype "bidirectional"))
    )
    (net (code "55") (name "FMC_D4") (class "Default")
      (node (ref "IC3") (pin "68") (pinfunction "PE7_68") (pintype "bidirectional"))
      (node (ref "IC6") (pin "8") (pinfunction "DQ4_8") (pintype "bidirectional"))
    )
    (net (code "56") (name "FMC_D5") (class "Default")
      (node (ref "IC3") (pin "69") (pinfunction "PE8_69") (pintype "bidirectional"))
      (node (ref "IC6") (pin "10") (pinfunction "DQ5_10") (pintype "bidirectional"))
    )
    (net (code "57") (name "FMC_D6") (class "Default")
      (node (ref "IC3") (pin "70") (pinfunction "PE9_70") (pintype "bidirectional"))
      (node (ref "IC6") (pin "11") (pinfunction "DQ6_11") (pintype "bidirectional"))
    )
    (net (code "58") (name "FMC_D7") (class "Default")
      (node (ref "IC3") (pin "73") (pinfunction "PE10_73") (pintype "bidirectional"))
      (node (ref "IC6") (pin "13") (pinfunction "DQ7_13") (pintype "bidirectional"))
    )
    (net (code "59") (name "FMC_D8") (class "Default")
      (node (ref "IC3") (pin "74") (pinfunction "PE11_74") (pintype "bidirectional"))
      (node (ref "IC6") (pin "42") (pinfunction "DQ8_42") (pintype "bidirectional"))
    )
    (net (code "60") (name "FMC_D9") (class "Default")
      (node (ref "IC3") (pin "75") (pinfunction "PE12_75") (pintype "bidirectional"))
      (node (ref "IC6") (pin "44") (pinfunction "DQ9_44") (pintype "bidirectional"))
    )
    (net (code "61") (name "FMC_D10") (class "Default")
      (node (ref "IC3") (pin "76") (pinfunction "PE13_76") (pintype "bidirectional"))
      (node (ref "IC6") (pin "45") (pinfunction "DQ10_45") (pintype "bidirectional"))
    )
    (net (code "62") (name "FMC_D11") (class "Default")
      (node (ref "IC3") (pin "77") (pinfunction "PE14_77") (pintype "bidirectional"))
      (node (ref "IC6") (pin "47") (pinfunction "DQ11_47") (pintype "bidirectional"))
    )
    (net (code "63") (name "FMC_D12") (class "Default")
      (node (ref "IC3") (pin "78") (pinfunction "PE15_78") (pintype "bidirectional"))
      (node (ref "IC6") (pin "48") (pinfunction "DQ12_48") (pintype "bidirectional"))
    )
    (net (code "64") (name "FMC_D13") (class "Default")
      (node (ref "IC3") (pin "89") (pinfunction "PD8_89") (pintype "bidirectional"))
      (node (ref "IC6") (pin "50") (pinfunction "DQ13_50") (pintype "bidirectional"))
    )
    (net (code "65") (name "FMC_D14") (class "Default")
      (node (ref "IC3") (pin "90") (pinfunction "PD9_90") (pintype "bidirectional"))
      (node (ref "IC6") (pin "51") (pinfunction "DQ14_51") (pintype "bidirectional"))
    )
    (net (code "66") (name "FMC_D15") (class "Default")
      (node (ref "IC3") (pin "91") (pinfunction "PD10_91") (pintype "bidirectional"))
      (node (ref "IC6") (pin "53") (pinfunction "DQ15_53") (pintype "bidirectional"))
    )
    (net (code "67") (name "FMC_NBL0") (class "Default")
      (node (ref "IC3") (pin "169") (pinfunction "PE0_169") (pintype "bidirectional"))
      (node (ref "IC6") (pin "15") (pinfunction "LDQM_15") (pintype "input"))
    )
    (net (code "68") (name "FMC_NBL1") (class "Default")
      (node (ref "IC3") (pin "170") (pinfunction "PE1_170") (pintype "bidirectional"))
      (node (ref "IC6") (pin "39") (pinfunction "UDQM_39") (pintype "input"))
    )
    (net (code "69") (name "FMC_SDCKE0") (class "Default")
      (node (ref "IC3") (pin "43") (pinfunction "PH2_43") (pintype "bidirectional"))
      (node (ref "IC6") (pin "37") (pinfunction "CKE_37") (pintype "input"))
    )
    (net (code "70") (name "FMC_SDCLK") (class "Default")
      (node (ref "IC3") (pin "116") (pinfunction "PG8_116") (pintype "bidirectional"))
      (node (ref "IC6") (pin "38") (pinfunction "CLK_38") (pintype "input"))
    )
    (net (code "71") (name "FMC_SDNCAS") (class "Default")
      (node (ref "IC3") (pin "160") (pinfunction "PG15_160") (pintype "bidirectional"))
      (node (ref "IC6") (pin "17") (pinfunction "~{CAS}_17") (pintype "input"))
    )
    (net (code "72") (name "FMC_SDNE0") (class "Default")
      (node (ref "IC3") (pin "44") (pinfunction "PH3_44") (pintype "bidirectional"))
      (node (ref "IC6") (pin "19") (pinfunction "~{CS}_19") (pintype "input"))
    )
    (net (code "73") (name "FMC_SDNRAS") (class "Default")
      (node (ref "IC3") (pin "59") (pinfunction "PF11_59") (pintype "bidirectional"))
      (node (ref "IC6") (pin "18") (pinfunction "~{RAS}_18") (pintype "input"))
    )
    (net (code "74") (name "FMC_SDNWE") (class "Default")
      (node (ref "IC3") (pin "46") (pinfunction "PH5_46") (pintype "bidirectional"))
      (node (ref "IC6") (pin "16") (pinfunction "~{WE}_16") (pintype "input"))
    )
    (net (code "75") (name "GND") (class "Default")
      (node (ref "B1") (pin "2") (pinfunction "-_2") (pintype "passive"))
      (node (ref "C1") (pin "2") (pinfunction "2_2") (pintype "passive"))
      (node (ref "C10") (pin "2") (pinfunction "2_2") (pintype "passive"))
      (node (ref "C11") (pin "1") (pinfunction "1_1") (pintype "passive"))
      (node (ref "C12") (pin "2") (pinfunction "2_2") (pintype "passive"))
      (node (ref "C13") (pin "2") (pinfunction "-_2") (pintype "passive"))
      (node (ref "C14") (pin "2") (pinfunction "2_2") (pintype "passive"))
      (node (ref "C15") (pin "-") (pinfunction "-_-") (pintype "passive"))
      (node (ref "C16") (pin "2") (pinfunction "2_2") (pintype "passive"))
      (node (ref "C17") (pin "2") (pinfunction "2_2") (pintype "passive"))
      (node (ref "C18") (pin "2") (pinfunction "2_2") (pintype "passive"))
      (node (ref "C19") (pin "2") (pinfunction "2_2") (pintype "passive"))
      (node (ref "C2") (pin "2") (pinfunction "2_2") (pintype "passive"))
      (node (ref "C20") (pin "2") (pinfunction "2_2") (pintype "passive"))
      (node (ref "C21") (pin "2") (pinfunction "2_2") (pintype "passive"))
      (node (ref "C22") (pin "-") (pinfunction "-_-") (pintype "passive"))
      (node (ref "C23") (pin "2") (pinfunction "2_2") (pintype "passive"))
      (node (ref "C24") (pin "2") (pinfunction "2_2") (pintype "passive"))
      (node (ref "C25") (pin "2") (pinfunction "2_2") (pintype "passive"))
      (node (ref "C26") (pin "2") (pinfunction "2_2") (pintype "passive"))
      (node (ref "C27") (pin "2") (pinfunction "2_2") (pintype "passive"))
      (node (ref "C28") (pin "2") (pinfunction "2_2") (pintype "passive"))
      (node (ref "C29") (pin "2") (pinfunction "2_2") (pintype "passive"))
      (node (ref "C3") (pin "1") (pinfunction "1_1") (pintype "passive"))
      (node (ref "C30") (pin "2") (pinfunction "2_2") (pintype "passive"))
      (node (ref "C31") (pin "2") (pinfunction "2_2") (pintype "passive"))
      (node (ref "C32") (pin "2") (pinfunction "2_2") (pintype "passive"))
      (node (ref "C33") (pin "2") (pinfunction "2_2") (pintype "passive"))
      (node (ref "C34") (pin "2") (pinfunction "2_2") (pintype "passive"))
      (node (ref "C35") (pin "2") (pinfunction "2_2") (pintype "passive"))
      (node (ref "C36") (pin "2") (pinfunction "2_2") (pintype "passive"))
      (node (ref "C37") (pin "2") (pinfunction "2_2") (pintype "passive"))
      (node (ref "C38") (pin "2") (pinfunction "2_2") (pintype "passive"))
      (node (ref "C39") (pin "2") (pinfunction "2_2") (pintype "passive"))
      (node (ref "C4") (pin "1") (pinfunction "1_1") (pintype "passive"))
      (node (ref "C40") (pin "1") (pinfunction "1_1") (pintype "passive"))
      (node (ref "C41") (pin "2") (pinfunction "2_2") (pintype "passive"))
      (node (ref "C42") (pin "2") (pinfunction "2_2") (pintype "passive"))
      (node (ref "C43") (pin "2") (pinfunction "2_2") (pintype "passive"))
      (node (ref "C44") (pin "2") (pinfunction "2_2") (pintype "passive"))
      (node (ref "C45") (pin "2") (pinfunction "2_2") (pintype "passive"))
      (node (ref "C46") (pin "2") (pinfunction "2_2") (pintype "passive"))
      (node (ref "C47") (pin "2") (pinfunction "2_2") (pintype "passive"))
      (node (ref "C48") (pin "2") (pinfunction "2_2") (pintype "passive"))
      (node (ref "C49") (pin "-") (pinfunction "-_-") (pintype "passive"))
      (node (ref "C5") (pin "2") (pinfunction "2_2") (pintype "passive"))
      (node (ref "C50") (pin "2") (pinfunction "2_2") (pintype "passive"))
      (node (ref "C51") (pin "2") (pinfunction "2_2") (pintype "passive"))
      (node (ref "C52") (pin "1") (pinfunction "1_1") (pintype "passive"))
      (node (ref "C53") (pin "1") (pinfunction "1_1") (pintype "passive"))
      (node (ref "C54") (pin "1") (pinfunction "1_1") (pintype "passive"))
      (node (ref "C55") (pin "1") (pinfunction "1_1") (pintype "passive"))
      (node (ref "C56") (pin "1") (pinfunction "1_1") (pintype "passive"))
      (node (ref "C57") (pin "2") (pinfunction "2_2") (pintype "passive"))
      (node (ref "C58") (pin "2") (pinfunction "2_2") (pintype "passive"))
      (node (ref "C59") (pin "1") (pinfunction "1_1") (pintype "passive"))
      (node (ref "C6") (pin "1") (pinfunction "1_1") (pintype "passive"))
      (node (ref "C60") (pin "2") (pinfunction "2_2") (pintype "passive"))
      (node (ref "C61") (pin "1") (pinfunction "1_1") (pintype "passive"))
      (node (ref "C62") (pin "2") (pinfunction "2_2") (pintype "passive"))
      (node (ref "C63") (pin "2") (pinfunction "2_2") (pintype "passive"))
      (node (ref "C64") (pin "-") (pinfunction "-_-") (pintype "passive"))
      (node (ref "C65") (pin "2") (pinfunction "2_2") (pintype "passive"))
      (node (ref "C66") (pin "2") (pinfunction "2_2") (pintype "passive"))
      (node (ref "C67") (pin "2") (pinfunction "2_2") (pintype "passive"))
      (node (ref "C68") (pin "2") (pinfunction "2_2") (pintype "passive"))
      (node (ref "C7") (pin "2") (pinfunction "2_2") (pintype "passive"))
      (node (ref "C9") (pin "1") (pinfunction "1_1") (pintype "passive"))
      (node (ref "D1") (pin "A") (pinfunction "A_A") (pintype "passive"))
      (node (ref "IC1") (pin "3") (pinfunction "GND_3") (pintype "power_in"))
      (node (ref "IC10") (pin "3") (pinfunction "GND_3") (pintype "power_in"))
      (node (ref "IC11") (pin "3") (pinfunction "GND_3") (pintype "power_in"))
      (node (ref "IC12") (pin "13") (pinfunction "A1_13") (pintype "input"))
      (node (ref "IC12") (pin "14") (pinfunction "A0_14") (pintype "input"))
      (node (ref "IC12") (pin "6") (pinfunction "GND_6") (pintype "passive"))
      (node (ref "IC13") (pin "3") (pinfunction "GND_3") (pintype "power_in"))
      (node (ref "IC14") (pin "15") (pinfunction "AGND-15_15") (pintype "power_in"))
      (node (ref "IC14") (pin "19") (pinfunction "AGND-19_19") (pintype "power_in"))
      (node (ref "IC14") (pin "35") (pinfunction "IOGND-35_35") (pintype "power_in"))
      (node (ref "IC14") (pin "36") (pinfunction "DGND_36") (pintype "power_in"))
      (node (ref "IC14") (pin "47") (pinfunction "IOGND-47_47") (pintype "power_in"))
      (node (ref "IC2") (pin "8") (pinfunction "VSS_8") (pintype "power_in"))
      (node (ref "IC3") (pin "103") (pinfunction "VSSDSI_2_103") (pintype "power_in"))
      (node (ref "IC3") (pin "109") (pinfunction "VSSDSI_109") (pintype "power_in"))
      (node (ref "IC3") (pin "117") (pinfunction "VSS_7_117") (pintype "power_in"))
      (node (ref "IC3") (pin "130") (pinfunction "VSS_8_130") (pintype "power_in"))
      (node (ref "IC3") (pin "135") (pinfunction "VSS_9_135") (pintype "power_in"))
      (node (ref "IC3") (pin "14") (pinfunction "VSS_2_14") (pintype "power_in"))
      (node (ref "IC3") (pin "148") (pinfunction "VSS_10_148") (pintype "power_in"))
      (node (ref "IC3") (pin "158") (pinfunction "VSS_158") (pintype "power_in"))
      (node (ref "IC3") (pin "22") (pinfunction "VSS_3_22") (pintype "power_in"))
      (node (ref "IC3") (pin "37") (pinfunction "VSSA_37") (pintype "power_in"))
      (node (ref "IC3") (pin "61") (pinfunction "VSS_4_61") (pintype "power_in"))
      (node (ref "IC3") (pin "71") (pinfunction "VSS_5_71") (pintype "power_in"))
      (node (ref "IC3") (pin "95") (pinfunction "VSS_6_95") (pintype "power_in"))
      (node (ref "IC4") (pin "1") (pinfunction "ADJ_1") (pintype "input"))
      (node (ref "IC5") (pin "3") (pinfunction "GND_3") (pintype "power_in"))
      (node (ref "IC6") (pin "12") (pinfunction "GNDQ-12_12") (pintype "power_in"))
      (node (ref "IC6") (pin "28") (pinfunction "GND-28_28") (pintype "power_in"))
      (node (ref "IC6") (pin "41") (pinfunction "GND_41") (pintype "power_in"))
      (node (ref "IC6") (pin "46") (pinfunction "GNDQ-46_46") (pintype "power_in"))
      (node (ref "IC6") (pin "52") (pinfunction "GNDQ-52_52") (pintype "power_in"))
      (node (ref "IC6") (pin "54") (pinfunction "GND-54_54") (pintype "power_in"))
      (node (ref "IC6") (pin "6") (pinfunction "GNDQ-6_6") (pintype "power_in"))
      (node (ref "IC7") (pin "1") (pinfunction "A0_1") (pintype "input"))
      (node (ref "IC7") (pin "2") (pinfunction "A1_2") (pintype "input"))
      (node (ref "IC7") (pin "3") (pinfunction "A2_3") (pintype "input"))
      (node (ref "IC7") (pin "4") (pinfunction "GND_4") (pintype "passive"))
      (node (ref "IC7") (pin "7") (pinfunction "WP_7") (pintype "input"))
      (node (ref "IC8") (pin "2") (pinfunction "GND_2") (pintype "power_in"))
      (node (ref "IC9") (pin "2") (pinfunction "GND_2") (pintype "power_in"))
      (node (ref "J1") (pin "6") (pinfunction "VSS_6") (pintype "power_in"))
      (node (ref "J1") (pin "S") (pinfunction "SH_S") (pintype "passive"))
      (node (ref "J1") (pin "S1") (pinfunction "SH_S1") (pintype "passive"))
      (node (ref "J1") (pin "S2") (pinfunction "SH_S2") (pintype "passive"))
      (node (ref "J1") (pin "SW2") (pinfunction "SW2_SW2") (pintype "passive"))
      (node (ref "J2") (pin "5") (pinfunction "GND_5") (pintype "passive"))
      (node (ref "JP1") (pin "1") (pinfunction "1_1") (pintype "passive"))
      (node (ref "JP6") (pin "NC") (pinfunction "NC_NC") (pintype "passive"))
      (node (ref "JP7") (pin "NC") (pinfunction "NC_NC") (pintype "passive"))
      (node (ref "LCD1") (pin "29") (pinfunction "GND-29_29") (pintype "power_in"))
      (node (ref "LCD1") (pin "3") (pinfunction "GND-3_3") (pintype "power_in"))
      (node (ref "Q1") (pin "E") (pinfunction "E_E") (pintype "passive"))
      (node (ref "Q2") (pin "2") (pinfunction "S_2") (pintype "passive"))
      (node (ref "R12") (pin "1") (pinfunction "1_1") (pintype "passive"))
      (node (ref "R13") (pin "1") (pinfunction "1_1") (pintype "passive"))
      (node (ref "R18") (pin "1") (pinfunction "1_1") (pintype "passive"))
      (node (ref "R25") (pin "2") (pinfunction "2_2") (pintype "passive"))
      (node (ref "R34") (pin "1") (pinfunction "1_1") (pintype "passive"))
      (node (ref "R37") (pin "1") (pinfunction "1_1") (pintype "passive"))
      (node (ref "R47") (pin "1") (pinfunction "1_1") (pintype "passive"))
      (node (ref "SW1") (pin "2") (pinfunction "2_2") (pintype "passive"))
      (node (ref "SW2") (pin "C") (pinfunction "C_C") (pintype "passive"))
      (node (ref "SW2") (pin "D") (pinfunction "1_D") (pintype "passive"))
      (node (ref "SW2") (pin "GND1") (pinfunction "C_GND1") (pintype "passive"))
      (node (ref "SW2") (pin "GND2") (pinfunction "C_GND2") (pintype "passive"))
      (node (ref "TP1") (pin "1") (pinfunction "P$1_1") (pintype "bidirectional"))
      (node (ref "X1") (pin "1") (pinfunction "1_1") (pintype "passive"))
      (node (ref "X1") (pin "15") (pinfunction "1_15") (pintype "passive"))
      (node (ref "X1") (pin "16") (pinfunction "1_16") (pintype "passive"))
      (node (ref "X1") (pin "2") (pinfunction "1_2") (pintype "passive"))
      (node (ref "X1") (pin "29") (pinfunction "1_29") (pintype "passive"))
      (node (ref "X1") (pin "30") (pinfunction "1_30") (pintype "passive"))
      (node (ref "X1") (pin "34") (pinfunction "1_34") (pintype "passive"))
      (node (ref "X1") (pin "39") (pinfunction "1_39") (pintype "passive"))
      (node (ref "X1") (pin "40") (pinfunction "1_40") (pintype "passive"))
      (node (ref "X2") (pin "7") (pinfunction "1_7") (pintype "passive"))
      (node (ref "X2") (pin "8") (pinfunction "1_8") (pintype "passive"))
      (node (ref "X2") (pin "9") (pinfunction "1_9") (pintype "passive"))
      (node (ref "X3") (pin "3") (pinfunction "1_3") (pintype "passive"))
      (node (ref "X4") (pin "3") (pinfunction "S_3") (pintype "passive"))
      (node (ref "X5") (pin "4") (pinfunction "GND_4") (pintype "passive"))
      (node (ref "X5") (pin "5") (pinfunction "GND_5") (pintype "passive"))
    )
    (net (code "76") (name "I2C1_SCL") (class "Default")
      (node (ref "IC12") (pin "12") (pinfunction "SCL_12") (pintype "bidirectional"))
      (node (ref "IC3") (pin "164") (pinfunction "PB6_164") (pintype "bidirectional"))
      (node (ref "IC7") (pin "6") (pinfunction "SCL_6") (pintype "bidirectional"))
      (node (ref "R15") (pin "2") (pinfunction "2_2") (pintype "passive"))
      (node (ref "SCL") (pin "1") (pinfunction "1_1") (pintype "passive"))
      (node (ref "X1") (pin "12") (pinfunction "1_12") (pintype "passive"))
    )
    (net (code "77") (name "I2C1_SDA") (class "Default")
      (node (ref "IC12") (pin "11") (pinfunction "SDA_11") (pintype "bidirectional"))
      (node (ref "IC3") (pin "165") (pinfunction "PB7_165") (pintype "bidirectional"))
      (node (ref "IC7") (pin "5") (pinfunction "SDA_5") (pintype "bidirectional"))
      (node (ref "R16") (pin "2") (pinfunction "2_2") (pintype "passive"))
      (node (ref "SDA") (pin "2") (pinfunction "2_2") (pintype "passive"))
      (node (ref "X1") (pin "14") (pinfunction "1_14") (pintype "passive"))
    )
    (net (code "78") (name "IRQ_TOUCH") (class "Default")
      (node (ref "IC12") (pin "10") (pinfunction "~{PENIRQ}_10") (pintype "output"))
      (node (ref "IC3") (pin "151") (pinfunction "PD7_151") (pintype "bidirectional"))
    )
    (net (code "79") (name "LCD_DISP") (class "Default")
      (node (ref "LCD1") (pin "31") (pinfunction "DISP_31") (pintype "input"))
      (node (ref "R30") (pin "1") (pinfunction "1_1") (pintype "passive"))
    )
    (net (code "80") (name "LED_ACT") (class "Default")
      (node (ref "IC14") (pin "26") (pinfunction "AN_EN(LED_ACT/COL)_26") (pintype "output"))
      (node (ref "R35") (pin "2") (pinfunction "2_2") (pintype "passive"))
      (node (ref "R43") (pin "2") (pinfunction "2_2") (pintype "passive"))
    )
    (net (code "81") (name "LED_LINK") (class "Default")
      (node (ref "IC14") (pin "28") (pinfunction "AN_0(LED_LINK)_28") (pintype "output"))
      (node (ref "R42") (pin "2") (pinfunction "2_2") (pintype "passive"))
      (node (ref "R44") (pin "2") (pinfunction "2_2") (pintype "passive"))
    )
    (net (code "82") (name "LED_SPEED") (class "Default")
      (node (ref "IC14") (pin "27") (pinfunction "AN_1(LED_SPEED)_27") (pintype "output"))
      (node (ref "R40") (pin "2") (pinfunction "2_2") (pintype "passive"))
      (node (ref "SPEED") (pin "C") (pinfunction "C_C") (pintype "passive"))
    )
    (net (code "83") (name "LTDC_B3") (class "Default")
      (node (ref "IC3") (pin "154") (pinfunction "PG11_154") (pintype "bidirectional"))
      (node (ref "LCD1") (pin "24") (pinfunction "B3_24") (pintype "input"))
    )
    (net (code "84") (name "LTDC_B4") (class "Default")
      (node (ref "IC3") (pin "155") (pinfunction "PG12_155") (pintype "bidirectional"))
      (node (ref "LCD1") (pin "25") (pinfunction "B4_25") (pintype "input"))
    )
    (net (code "85") (name "LTDC_B5") (class "Default")
      (node (ref "IC3") (pin "174") (pinfunction "PI5_174") (pintype "bidirectional"))
      (node (ref "LCD1") (pin "26") (pinfunction "B5_26") (pintype "input"))
    )
    (net (code "86") (name "LTDC_B6") (class "Default")
      (node (ref "IC3") (pin "175") (pinfunction "PI6_175") (pintype "bidirectional"))
      (node (ref "LCD1") (pin "27") (pinfunction "B6_27") (pintype "input"))
    )
    (net (code "87") (name "LTDC_B7") (class "Default")
      (node (ref "IC3") (pin "176") (pinfunction "PI7_176") (pintype "bidirectional"))
      (node (ref "LCD1") (pin "28") (pinfunction "B7_28") (pintype "input"))
    )
    (net (code "88") (name "LTDC_CLK") (class "Default")
      (node (ref "IC3") (pin "115") (pinfunction "PG7_115") (pintype "bidirectional"))
      (node (ref "LCD1") (pin "30") (pinfunction "CLK_30") (pintype "input"))
    )
    (net (code "89") (name "LTDC_DE") (class "Default")
      (node (ref "IC3") (pin "28") (pinfunction "PF10_28") (pintype "bidirectional"))
      (node (ref "LCD1") (pin "34") (pinfunction "DE/NC2_34") (pintype "passive"))
    )
    (net (code "90") (name "LTDC_G2") (class "Default")
      (node (ref "IC3") (pin "52") (pinfunction "PA6_52") (pintype "bidirectional"))
      (node (ref "LCD1") (pin "15") (pinfunction "G2_15") (pintype "input"))
    )
    (net (code "91") (name "LTDC_G3") (class "Default")
      (node (ref "IC3") (pin "153") (pinfunction "PG10_153") (pintype "bidirectional"))
      (node (ref "LCD1") (pin "16") (pinfunction "G3_16") (pintype "input"))
    )
    (net (code "92") (name "LTDC_G4") (class "Default")
      (node (ref "IC3") (pin "45") (pinfunction "PH4_45") (pintype "bidirectional"))
      (node (ref "LCD1") (pin "17") (pinfunction "G4_17") (pintype "input"))
    )
    (net (code "93") (name "LTDC_G5") (class "Default")
      (node (ref "IC3") (pin "132") (pinfunction "PI0_132") (pintype "bidirectional"))
      (node (ref "LCD1") (pin "18") (pinfunction "G5_18") (pintype "input"))
    )
    (net (code "94") (name "LTDC_G6") (class "Default")
      (node (ref "IC3") (pin "13") (pinfunction "PI11_13") (pintype "bidirectional"))
      (node (ref "LCD1") (pin "19") (pinfunction "G6_19") (pintype "input"))
    )
    (net (code "95") (name "LTDC_G7") (class "Default")
      (node (ref "IC3") (pin "145") (pinfunction "PD3_145") (pintype "bidirectional"))
      (node (ref "LCD1") (pin "20") (pinfunction "G7_20") (pintype "input"))
    )
    (net (code "96") (name "LTDC_HSYNC") (class "Default")
      (node (ref "IC3") (pin "12") (pinfunction "PI10_12") (pintype "bidirectional"))
      (node (ref "LCD1") (pin "32") (pinfunction "HSYNC_32") (pintype "input"))
    )
    (net (code "97") (name "LTDC_R3") (class "Default")
      (node (ref "IC3") (pin "56") (pinfunction "PB0_56") (pintype "bidirectional"))
      (node (ref "LCD1") (pin "8") (pinfunction "R3_8") (pintype "input"))
    )
    (net (code "98") (name "LTDC_R4") (class "Default")
      (node (ref "IC3") (pin "51") (pinfunction "PA5_51") (pintype "bidirectional"))
      (node (ref "LCD1") (pin "9") (pinfunction "R4_9") (pintype "input"))
    )
    (net (code "99") (name "LTDC_R5") (class "Default")
      (node (ref "IC3") (pin "32") (pinfunction "PC0_32") (pintype "bidirectional"))
      (node (ref "LCD1") (pin "10") (pinfunction "R5_10") (pintype "input"))
    )
    (net (code "100") (name "LTDC_R6") (class "Default")
      (node (ref "IC3") (pin "57") (pinfunction "PB1_57") (pintype "bidirectional"))
      (node (ref "LCD1") (pin "11") (pinfunction "R6_11") (pintype "input"))
    )
    (net (code "101") (name "LTDC_R7") (class "Default")
      (node (ref "IC3") (pin "114") (pinfunction "PG6_114") (pintype "bidirectional"))
      (node (ref "LCD1") (pin "12") (pinfunction "R7_12") (pintype "input"))
    )
    (net (code "102") (name "LTDC_VSYNC") (class "Default")
      (node (ref "IC3") (pin "11") (pinfunction "PI9_11") (pintype "bidirectional"))
      (node (ref "LCD1") (pin "33") (pinfunction "VSYNC_33") (pintype "input"))
    )
    (net (code "103") (name "MCLK_25") (class "Default")
      (node (ref "IC3") (pin "122") (pinfunction "PC9_122") (pintype "bidirectional"))
      (node (ref "RN1") (pin "1") (pinfunction "1_1") (pintype "passive"))
    )
    (net (code "104") (name "Net-(B1-+-Pad1)") (class "Default")
      (node (ref "B1") (pin "1") (pinfunction "+_1") (pintype "passive"))
      (node (ref "B1") (pin "3") (pinfunction "+_3") (pintype "passive"))
      (node (ref "JP3") (pin "1") (pinfunction "1_1") (pintype "passive"))
      (node (ref "JP4") (pin "NC") (pinfunction "NC_NC") (pintype "passive"))
    )
    (net (code "105") (name "Net-(C53-Pad2)") (class "Default")
      (node (ref "C53") (pin "2") (pinfunction "2_2") (pintype "passive"))
      (node (ref "JP8") (pin "COM") (pinfunction "COM_COM") (pintype "passive"))
      (node (ref "SP1") (pin "+B") (pinfunction "+_+B") (pintype "passive"))
      (node (ref "SP1") (pin "+B.1") (pinfunction "+_+B.1") (pintype "passive"))
    )
    (net (code "106") (name "Net-(C58-Pad1)") (class "Default")
      (node (ref "C58") (pin "1") (pinfunction "1_1") (pintype "passive"))
      (node (ref "R32") (pin "1") (pinfunction "1_1") (pintype "passive"))
      (node (ref "R33") (pin "2") (pinfunction "2_2") (pintype "passive"))
    )
    (net (code "107") (name "Net-(C60-Pad1)") (class "Default")
      (node (ref "C60") (pin "1") (pinfunction "1_1") (pintype "passive"))
      (node (ref "R36") (pin "1") (pinfunction "1_1") (pintype "passive"))
      (node (ref "R41") (pin "2") (pinfunction "2_2") (pintype "passive"))
    )
    (net (code "108") (name "Net-(IC1-IO1)") (class "Default")
      (node (ref "IC1") (pin "1") (pinfunction "IO1_1") (pintype "bidirectional"))
      (node (ref "R3") (pin "1") (pinfunction "1_1") (pintype "passive"))
      (node (ref "X3") (pin "1") (pinfunction "1_1") (pintype "passive"))
    )
    (net (code "109") (name "Net-(IC1-IO2)") (class "Default")
      (node (ref "IC1") (pin "2") (pinfunction "IO2_2") (pintype "bidirectional"))
      (node (ref "R7") (pin "1") (pinfunction "1_1") (pintype "passive"))
      (node (ref "X3") (pin "2") (pinfunction "1_2") (pintype "passive"))
    )
    (net (code "110") (name "Net-(IC1-IO3)") (class "Default")
      (node (ref "IC1") (pin "4") (pinfunction "IO3_4") (pintype "bidirectional"))
      (node (ref "IC2") (pin "12") (pinfunction "O_12") (pintype "output"))
      (node (ref "IC2") (pin "4") (pinfunction "O_4") (pintype "output"))
      (node (ref "X3") (pin "4") (pinfunction "1_4") (pintype "passive"))
    )
    (net (code "111") (name "Net-(IC1-IO4)") (class "Default")
      (node (ref "IC1") (pin "5") (pinfunction "IO4_5") (pintype "bidirectional"))
      (node (ref "IC2") (pin "10") (pinfunction "O_10") (pintype "output"))
      (node (ref "IC2") (pin "6") (pinfunction "O_6") (pintype "output"))
      (node (ref "X3") (pin "5") (pinfunction "1_5") (pintype "passive"))
    )
    (net (code "112") (name "Net-(IC2A-I)") (class "Default")
      (node (ref "IC2") (pin "3") (pinfunction "I_3") (pintype "input"))
      (node (ref "R8") (pin "2") (pinfunction "2_2") (pintype "passive"))
    )
    (net (code "113") (name "Net-(IC2A-O)") (class "Default")
      (node (ref "IC2") (pin "2") (pinfunction "O_2") (pintype "output"))
      (node (ref "R9") (pin "1") (pinfunction "1_1") (pintype "passive"))
    )
    (net (code "114") (name "Net-(IC2F-I)") (class "Default")
      (node (ref "IC2") (pin "14") (pinfunction "I_14") (pintype "input"))
      (node (ref "R4") (pin "2") (pinfunction "2_2") (pintype "passive"))
    )
    (net (code "115") (name "Net-(IC2F-O)") (class "Default")
      (node (ref "IC2") (pin "15") (pinfunction "O_15") (pintype "output"))
      (node (ref "R5") (pin "1") (pinfunction "1_1") (pintype "passive"))
    )
    (net (code "116") (name "Net-(IC3D-VCAPDSI)") (class "Default")
      (node (ref "IC3") (pin "100") (pinfunction "VCAPDSI_100") (pintype "power_in"))
      (node (ref "IC3") (pin "106") (pinfunction "VDD12DSI_106") (pintype "power_in"))
    )
    (net (code "117") (name "Net-(IC9-SW)") (class "Default")
      (node (ref "D2") (pin "A") (pinfunction "A_A") (pintype "passive"))
      (node (ref "IC9") (pin "1") (pinfunction "SW_1") (pintype "output"))
      (node (ref "L1") (pin "2") (pinfunction "2_2") (pintype "passive"))
    )
    (net (code "118") (name "Net-(IC9-VIN)") (class "Default")
      (node (ref "IC9") (pin "5") (pinfunction "VIN_5") (pintype "input"))
      (node (ref "R23") (pin "2") (pinfunction "2_2") (pintype "passive"))
    )
    (net (code "119") (name "Net-(IC13-IO1)") (class "Default")
      (node (ref "IC13") (pin "1") (pinfunction "IO1_1") (pintype "bidirectional"))
      (node (ref "IC14") (pin "17") (pinfunction "TD+_17") (pintype "bidirectional"))
      (node (ref "R32") (pin "2") (pinfunction "2_2") (pintype "passive"))
      (node (ref "X5") (pin "1") (pinfunction "TD+_1") (pintype "input"))
    )
    (net (code "120") (name "Net-(IC13-IO2)") (class "Default")
      (node (ref "IC13") (pin "2") (pinfunction "IO2_2") (pintype "bidirectional"))
      (node (ref "IC14") (pin "16") (pinfunction "TD-_16") (pintype "bidirectional"))
      (node (ref "R33") (pin "1") (pinfunction "1_1") (pintype "passive"))
      (node (ref "X5") (pin "2") (pinfunction "TD-_2") (pintype "input"))
    )
    (net (code "121") (name "Net-(IC13-IO3)") (class "Default")
      (node (ref "IC13") (pin "4") (pinfunction "IO3_4") (pintype "bidirectional"))
      (node (ref "IC14") (pin "14") (pinfunction "RD+_14") (pintype "bidirectional"))
      (node (ref "R36") (pin "2") (pinfunction "2_2") (pintype "passive"))
      (node (ref "X5") (pin "7") (pinfunction "RD+_7") (pintype "input"))
    )
    (net (code "122") (name "Net-(IC13-IO4)") (class "Default")
      (node (ref "IC13") (pin "5") (pinfunction "IO4_5") (pintype "bidirectional"))
      (node (ref "IC14") (pin "13") (pinfunction "RD-_13") (pintype "bidirectional"))
      (node (ref "R41") (pin "1") (pinfunction "1_1") (pintype "passive"))
      (node (ref "X5") (pin "8") (pinfunction "RD-_8") (pintype "input"))
    )
    (net (code "123") (name "Net-(IC14-CRS{slash}CRS_DV{slash}LED_CFG)") (class "Default")
      (node (ref "IC14") (pin "40") (pinfunction "CRS/CRS_DV/LED_CFG_40") (pintype "output"))
      (node (ref "RN1") (pin "5") (pinfunction "2_5") (pintype "passive"))
    )
    (net (code "124") (name "Net-(IC14-MDIX_EN(RX_ER))") (class "Default")
      (node (ref "IC14") (pin "41") (pinfunction "MDIX_EN(RX_ER)_41") (pintype "output"))
      (node (ref "RN2") (pin "8") (pinfunction "2_8") (pintype "passive"))
    )
    (net (code "125") (name "Net-(IC14-MII_MODE(RX_DV))") (class "Default")
      (node (ref "IC14") (pin "39") (pinfunction "MII_MODE(RX_DV)_39") (pintype "output"))
      (node (ref "JP11") (pin "2") (pinfunction "2_2") (pintype "passive"))
      (node (ref "RN1") (pin "6") (pinfunction "2_6") (pintype "passive"))
    )
    (net (code "126") (name "Net-(IC14-PFBIN1)") (class "Default")
      (node (ref "C62") (pin "1") (pinfunction "1_1") (pintype "passive"))
      (node (ref "C63") (pin "1") (pinfunction "1_1") (pintype "passive"))
      (node (ref "C64") (pin "+") (pinfunction "+_+") (pintype "passive"))
      (node (ref "C65") (pin "1") (pinfunction "1_1") (pintype "passive"))
      (node (ref "IC14") (pin "18") (pinfunction "PFBIN1_18") (pintype "input"))
      (node (ref "IC14") (pin "23") (pinfunction "PFBOUT_23") (pintype "output"))
      (node (ref "IC14") (pin "37") (pinfunction "PFBIN2_37") (pintype "input"))
    )
    (net (code "127") (name "Net-(IC14-PHYAD0(COL))") (class "Default")
      (node (ref "IC14") (pin "42") (pinfunction "PHYAD0(COL)_42") (pintype "output"))
      (node (ref "RN2") (pin "7") (pinfunction "2_7") (pintype "passive"))
    )
    (net (code "128") (name "Net-(IC14-PHYAD1(RXD1_0))") (class "Default")
      (node (ref "IC14") (pin "43") (pinfunction "PHYAD1(RXD1_0)_43") (pintype "output"))
      (node (ref "RN2") (pin "6") (pinfunction "2_6") (pintype "passive"))
    )
    (net (code "129") (name "Net-(IC14-PHYAD2(RXD1_1))") (class "Default")
      (node (ref "IC14") (pin "44") (pinfunction "PHYAD2(RXD1_1)_44") (pintype "output"))
      (node (ref "RN2") (pin "5") (pinfunction "2_5") (pintype "passive"))
    )
    (net (code "130") (name "Net-(IC14-PHYAD3(RXD1_2))") (class "Default")
      (node (ref "IC14") (pin "45") (pinfunction "PHYAD3(RXD1_2)_45") (pintype "output"))
      (node (ref "RN3") (pin "8") (pinfunction "2_8") (pintype "passive"))
    )
    (net (code "131") (name "Net-(IC14-PHYAD4(RXD1_3))") (class "Default")
      (node (ref "IC14") (pin "46") (pinfunction "PHYAD4(RXD1_3)_46") (pintype "output"))
      (node (ref "RN3") (pin "7") (pinfunction "2_7") (pintype "passive"))
    )
    (net (code "132") (name "Net-(IC14-PWR_DOWN{slash}INT)") (class "Default")
      (node (ref "IC14") (pin "7") (pinfunction "PWR_DOWN/INT_7") (pintype "input"))
      (node (ref "JP13") (pin "2") (pinfunction "2_2") (pintype "passive"))
    )
    (net (code "133") (name "Net-(IC14-RBIAS)") (class "Default")
      (node (ref "IC14") (pin "24") (pinfunction "RBIAS_24") (pintype "input"))
      (node (ref "R47") (pin "2") (pinfunction "2_2") (pintype "passive"))
    )
    (net (code "134") (name "Net-(IC14-RESERVED-20)") (class "Default")
      (node (ref "IC14") (pin "20") (pinfunction "RESERVED-20_20") (pintype "bidirectional"))
      (node (ref "R46") (pin "2") (pinfunction "2_2") (pintype "passive"))
    )
    (net (code "135") (name "Net-(IC14-RESERVED-21)") (class "Default")
      (node (ref "IC14") (pin "21") (pinfunction "RESERVED-21_21") (pintype "bidirectional"))
      (node (ref "R45") (pin "2") (pinfunction "2_2") (pintype "passive"))
    )
    (net (code "136") (name "Net-(IC14-RX_CLK)") (class "Default")
      (node (ref "IC14") (pin "38") (pinfunction "RX_CLK_38") (pintype "output"))
      (node (ref "RN1") (pin "7") (pinfunction "2_7") (pintype "passive"))
    )
    (net (code "137") (name "Net-(IC14-TXD_0)") (class "Default")
      (node (ref "IC14") (pin "3") (pinfunction "TXD_0_3") (pintype "input"))
      (node (ref "RN4") (pin "8") (pinfunction "2_8") (pintype "passive"))
    )
    (net (code "138") (name "Net-(IC14-TXD_1)") (class "Default")
      (node (ref "IC14") (pin "4") (pinfunction "TXD_1_4") (pintype "input"))
      (node (ref "RN4") (pin "7") (pinfunction "2_7") (pintype "passive"))
    )
    (net (code "139") (name "Net-(IC14-TXD_2)") (class "Default")
      (node (ref "IC14") (pin "5") (pinfunction "TXD_2_5") (pintype "input"))
      (node (ref "RN4") (pin "6") (pinfunction "2_6") (pintype "passive"))
    )
    (net (code "140") (name "Net-(IC14-TXD_3{slash}SNI_MODE)") (class "Default")
      (node (ref "IC14") (pin "6") (pinfunction "TXD_3/SNI_MODE_6") (pintype "input"))
      (node (ref "RN4") (pin "5") (pinfunction "2_5") (pintype "passive"))
    )
    (net (code "141") (name "Net-(IC14-TX_CLK)") (class "Default")
      (node (ref "IC14") (pin "1") (pinfunction "TX_CLK_1") (pintype "output"))
      (node (ref "RN3") (pin "6") (pinfunction "2_6") (pintype "passive"))
    )
    (net (code "142") (name "Net-(IC14-TX_EN)") (class "Default")
      (node (ref "IC14") (pin "2") (pinfunction "TX_EN_2") (pintype "input"))
      (node (ref "RN3") (pin "5") (pinfunction "2_5") (pintype "passive"))
    )
    (net (code "143") (name "Net-(IC14-X1)") (class "Default")
      (node (ref "IC14") (pin "34") (pinfunction "X1_34") (pintype "input"))
      (node (ref "RN1") (pin "8") (pinfunction "2_8") (pintype "passive"))
    )
    (net (code "144") (name "Net-(JP9-Pad2)") (class "Default")
      (node (ref "JP9") (pin "2") (pinfunction "2_2") (pintype "passive"))
      (node (ref "R37") (pin "2") (pinfunction "2_2") (pintype "passive"))
    )
    (net (code "145") (name "Net-(JP10-Pad1)") (class "Default")
      (node (ref "JP10") (pin "1") (pinfunction "1_1") (pintype "passive"))
      (node (ref "JP12") (pin "1") (pinfunction "1_1") (pintype "passive"))
      (node (ref "RN2") (pin "1") (pinfunction "1_1") (pintype "passive"))
    )
    (net (code "146") (name "Net-(JP10-Pad2)") (class "Default")
      (node (ref "JP10") (pin "2") (pinfunction "2_2") (pintype "passive"))
      (node (ref "R34") (pin "2") (pinfunction "2_2") (pintype "passive"))
    )
    (net (code "147") (name "Net-(JP11-Pad1)") (class "Default")
      (node (ref "JP11") (pin "1") (pinfunction "1_1") (pintype "passive"))
      (node (ref "R39") (pin "2") (pinfunction "2_2") (pintype "passive"))
    )
    (net (code "148") (name "Net-(JP13-Pad1)") (class "Default")
      (node (ref "JP13") (pin "1") (pinfunction "1_1") (pintype "passive"))
      (node (ref "R48") (pin "2") (pinfunction "2_2") (pintype "passive"))
    )
    (net (code "149") (name "Net-(LCD1-B0)") (class "Default")
      (node (ref "JP6") (pin "COM") (pinfunction "COM_COM") (pintype "passive"))
      (node (ref "LCD1") (pin "13") (pinfunction "G0_13") (pintype "input"))
      (node (ref "LCD1") (pin "14") (pinfunction "G1_14") (pintype "input"))
      (node (ref "LCD1") (pin "21") (pinfunction "B0_21") (pintype "input"))
      (node (ref "LCD1") (pin "22") (pinfunction "B1_22") (pintype "input"))
      (node (ref "LCD1") (pin "23") (pinfunction "B2_23") (pintype "input"))
      (node (ref "LCD1") (pin "5") (pinfunction "R0_5") (pintype "input"))
      (node (ref "LCD1") (pin "6") (pinfunction "R1_6") (pintype "input"))
      (node (ref "LCD1") (pin "7") (pinfunction "R2_7") (pintype "input"))
    )
    (net (code "150") (name "Net-(LCD1-RESET)") (class "Default")
      (node (ref "JP7") (pin "COM") (pinfunction "COM_COM") (pintype "passive"))
      (node (ref "LCD1") (pin "36") (pinfunction "RESET_36") (pintype "input"))
    )
    (net (code "151") (name "Net-(Q1-PadB)") (class "Default")
      (node (ref "Q1") (pin "B") (pinfunction "B_B") (pintype "passive"))
      (node (ref "R27") (pin "2") (pinfunction "2_2") (pintype "passive"))
    )
    (net (code "152") (name "Net-(Q1-PadC)") (class "Default")
      (node (ref "Q1") (pin "C") (pinfunction "C_C") (pintype "passive"))
      (node (ref "R24") (pin "1") (pinfunction "1_1") (pintype "passive"))
    )
    (net (code "153") (name "Net-(Q2-D)") (class "Default")
      (node (ref "Q2") (pin "3") (pinfunction "D_3") (pintype "passive"))
      (node (ref "SP1") (pin "-B") (pinfunction "-_-B") (pintype "passive"))
      (node (ref "SP1") (pin "-B.1") (pinfunction "-_-B.1") (pintype "passive"))
    )
    (net (code "154") (name "Net-(R1-Pad2)") (class "Default")
      (node (ref "R1") (pin "2") (pinfunction "2_2") (pintype "passive"))
      (node (ref "R2") (pin "2") (pinfunction "2_2") (pintype "passive"))
      (node (ref "SW2") (pin "A") (pinfunction "A_A") (pintype "passive"))
    )
    (net (code "155") (name "Net-(R3-Pad2)") (class "Default")
      (node (ref "R3") (pin "2") (pinfunction "2_2") (pintype "passive"))
      (node (ref "R4") (pin "1") (pinfunction "1_1") (pintype "passive"))
    )
    (net (code "156") (name "Net-(R7-Pad2)") (class "Default")
      (node (ref "R7") (pin "2") (pinfunction "2_2") (pintype "passive"))
      (node (ref "R8") (pin "1") (pinfunction "1_1") (pintype "passive"))
    )
    (net (code "157") (name "Net-(R10-Pad2)") (class "Default")
      (node (ref "R10") (pin "2") (pinfunction "2_2") (pintype "passive"))
      (node (ref "R6") (pin "2") (pinfunction "2_2") (pintype "passive"))
      (node (ref "SW2") (pin "B") (pinfunction "B_B") (pintype "passive"))
    )
    (net (code "158") (name "Net-(R24-Pad2)") (class "Default")
      (node (ref "R24") (pin "2") (pinfunction "2_2") (pintype "passive"))
      (node (ref "VBUS") (pin "C") (pinfunction "C_C") (pintype "passive"))
    )
    (net (code "159") (name "Net-(R38-Pad2)") (class "Default")
      (node (ref "R38") (pin "2") (pinfunction "2_2") (pintype "passive"))
      (node (ref "SPEED") (pin "A") (pinfunction "A_A") (pintype "passive"))
    )
    (net (code "160") (name "Net-(X2E-1)") (class "Default")
      (node (ref "SCL") (pin "2") (pinfunction "2_2") (pintype "passive"))
      (node (ref "X2") (pin "13") (pinfunction "1_13") (pintype "passive"))
    )
    (net (code "161") (name "Net-(X2F-1)") (class "Default")
      (node (ref "SDA") (pin "1") (pinfunction "1_1") (pintype "passive"))
      (node (ref "X2") (pin "14") (pinfunction "1_14") (pintype "passive"))
    )
    (net (code "162") (name "Net-(X4A-S)") (class "Default")
      (node (ref "JP5") (pin "2") (pinfunction "2_2") (pintype "passive"))
      (node (ref "R18") (pin "2") (pinfunction "2_2") (pintype "passive"))
      (node (ref "X4") (pin "1") (pinfunction "S_1") (pintype "passive"))
    )
    (net (code "163") (name "Net-(X5-GREEN-C)") (class "Default")
      (node (ref "R44") (pin "1") (pinfunction "1_1") (pintype "passive"))
      (node (ref "X5") (pin "10") (pinfunction "GREEN-C_10") (pintype "passive"))
    )
    (net (code "164") (name "Net-(X5-YELLOW-C)") (class "Default")
      (node (ref "R43") (pin "1") (pinfunction "1_1") (pintype "passive"))
      (node (ref "X5") (pin "11") (pinfunction "YELLOW-C_11") (pintype "passive"))
    )
    (net (code "165") (name "OE_SYNC") (class "Default")
      (node (ref "IC3") (pin "94") (pinfunction "PD13_94") (pintype "bidirectional"))
      (node (ref "X1") (pin "10") (pinfunction "1_10") (pintype "passive"))
    )
    (net (code "166") (name "PE") (class "Default")
      (node (ref "C1") (pin "1") (pinfunction "1_1") (pintype "passive"))
      (node (ref "C51") (pin "1") (pinfunction "1_1") (pintype "passive"))
      (node (ref "J2") (pin "SH1") (pinfunction "SH1_SH1") (pintype "bidirectional"))
      (node (ref "J2") (pin "SH1.1") (pinfunction "SH1_SH1.1") (pintype "bidirectional"))
      (node (ref "J2") (pin "SH2") (pinfunction "SH2_SH2") (pintype "bidirectional"))
      (node (ref "J2") (pin "SH2.2") (pinfunction "SH2_SH2.2") (pintype "bidirectional"))
      (node (ref "JP1") (pin "2") (pinfunction "2_2") (pintype "passive"))
      (node (ref "X2") (pin "1") (pinfunction "1_1") (pintype "passive"))
      (node (ref "X5") (pin "SH") (pinfunction "SH_SH") (pintype "passive"))
      (node (ref "X5") (pin "SH2") (pinfunction "SH_SH2") (pintype "passive"))
    )
    (net (code "167") (name "PWR_DIRECT") (class "Default")
      (node (ref "IC3") (pin "110") (pinfunction "PG2_110") (pintype "bidirectional"))
      (node (ref "X2") (pin "12") (pinfunction "1_12") (pintype "passive"))
    )
    (net (code "168") (name "PWR_SSTART") (class "Default")
      (node (ref "IC3") (pin "111") (pinfunction "PG3_111") (pintype "bidirectional"))
      (node (ref "X2") (pin "11") (pinfunction "1_11") (pintype "passive"))
    )
    (net (code "169") (name "RCC_OSC32_IN") (class "Default")
      (node (ref "C10") (pin "1") (pinfunction "1_1") (pintype "passive"))
      (node (ref "IC3") (pin "9") (pinfunction "PC14_9") (pintype "bidirectional"))
      (node (ref "Y2") (pin "1") (pinfunction "1_1") (pintype "passive"))
    )
    (net (code "170") (name "RCC_OSC32_OUT") (class "Default")
      (node (ref "C12") (pin "1") (pinfunction "1_1") (pintype "passive"))
      (node (ref "IC3") (pin "10") (pinfunction "PC15_10") (pintype "bidirectional"))
      (node (ref "Y2") (pin "4") (pinfunction "2_4") (pintype "passive"))
    )
    (net (code "171") (name "RCC_OSC_IN") (class "Default")
      (node (ref "C9") (pin "2") (pinfunction "2_2") (pintype "passive"))
      (node (ref "IC3") (pin "29") (pinfunction "PH0_29") (pintype "bidirectional"))
      (node (ref "Y1") (pin "2") (pinfunction "2_2") (pintype "passive"))
    )
    (net (code "172") (name "RCC_OSC_OUT") (class "Default")
      (node (ref "C11") (pin "2") (pinfunction "2_2") (pintype "passive"))
      (node (ref "IC3") (pin "30") (pinfunction "PH1_30") (pintype "bidirectional"))
      (node (ref "Y1") (pin "1") (pinfunction "1_1") (pintype "passive"))
    )
    (net (code "173") (name "SDMMC1_CK") (class "Default")
      (node (ref "IC3") (pin "141") (pinfunction "PC12_141") (pintype "bidirectional"))
      (node (ref "J1") (pin "5") (pinfunction "CLK_5") (pintype "passive"))
    )
    (net (code "174") (name "SDMMC1_CMD") (class "Default")
      (node (ref "IC3") (pin "144") (pinfunction "PD2_144") (pintype "bidirectional"))
      (node (ref "J1") (pin "3") (pinfunction "CMD_3") (pintype "passive"))
      (node (ref "R22") (pin "2") (pinfunction "2_2") (pintype "passive"))
    )
    (net (code "175") (name "SDMMC1_D0") (class "Default")
      (node (ref "IC3") (pin "121") (pinfunction "PC8_121") (pintype "bidirectional"))
      (node (ref "J1") (pin "7") (pinfunction "DAT0_7") (pintype "passive"))
      (node (ref "R21") (pin "2") (pinfunction "2_2") (pintype "passive"))
    )
    (net (code "176") (name "SD_DETECT") (class "Default")
      (node (ref "IC3") (pin "140") (pinfunction "PC11_140") (pintype "bidirectional"))
      (node (ref "J1") (pin "SW1") (pinfunction "SW1_SW1") (pintype "passive"))
    )
    (net (code "177") (name "SPI2_CLK") (class "Default")
      (node (ref "IC3") (pin "133") (pinfunction "PI1_133") (pintype "bidirectional"))
      (node (ref "X1") (pin "32") (pinfunction "1_32") (pintype "passive"))
    )
    (net (code "178") (name "SPI2_CSA") (class "Default")
      (node (ref "IC3") (pin "93") (pinfunction "PD12_93") (pintype "bidirectional"))
      (node (ref "X1") (pin "28") (pinfunction "1_28") (pintype "passive"))
    )
    (net (code "179") (name "SPI2_CSB") (class "Default")
      (node (ref "IC3") (pin "92") (pinfunction "PD11_92") (pintype "bidirectional"))
      (node (ref "X1") (pin "27") (pinfunction "1_27") (pintype "passive"))
    )
    (net (code "180") (name "SPI2_IRQ") (class "Default")
      (node (ref "IC3") (pin "123") (pinfunction "PA8_123") (pintype "bidirectional"))
      (node (ref "X1") (pin "25") (pinfunction "1_25") (pintype "passive"))
    )
    (net (code "181") (name "SPI2_MISO") (class "Default")
      (node (ref "IC3") (pin "87") (pinfunction "PB14_87") (pintype "bidirectional"))
      (node (ref "X1") (pin "31") (pinfunction "1_31") (pintype "passive"))
    )
    (net (code "182") (name "SPI2_MOSI") (class "Default")
      (node (ref "IC3") (pin "134") (pinfunction "PI3_134") (pintype "bidirectional"))
      (node (ref "X1") (pin "33") (pinfunction "1_33") (pintype "passive"))
    )
    (net (code "183") (name "SPI4_CLK") (class "Default")
      (node (ref "IC3") (pin "1") (pinfunction "PE2_1") (pintype "bidirectional"))
      (node (ref "X1") (pin "23") (pinfunction "1_23") (pintype "passive"))
    )
    (net (code "184") (name "SPI4_CSA") (class "Default")
      (node (ref "IC3") (pin "2") (pinfunction "PE3_2") (pintype "bidirectional"))
      (node (ref "X1") (pin "22") (pinfunction "1_22") (pintype "passive"))
    )
    (net (code "185") (name "SPI4_CSB") (class "Default")
      (node (ref "IC3") (pin "3") (pinfunction "PE4_3") (pintype "bidirectional"))
      (node (ref "X1") (pin "21") (pinfunction "1_21") (pintype "passive"))
    )
    (net (code "186") (name "SPI4_IRQ") (class "Default")
      (node (ref "IC3") (pin "168") (pinfunction "PB9_168") (pintype "bidirectional"))
      (node (ref "X1") (pin "19") (pinfunction "1_19") (pintype "passive"))
    )
    (net (code "187") (name "SPI4_MISO") (class "Default")
      (node (ref "IC3") (pin "4") (pinfunction "PE5_4") (pintype "bidirectional"))
      (node (ref "X1") (pin "24") (pinfunction "1_24") (pintype "passive"))
    )
    (net (code "188") (name "SPI4_MOSI") (class "Default")
      (node (ref "IC3") (pin "5") (pinfunction "PE6_5") (pintype "bidirectional"))
      (node (ref "X1") (pin "26") (pinfunction "1_26") (pintype "passive"))
    )
    (net (code "189") (name "SPI5_CLK") (class "Default")
      (node (ref "IC3") (pin "25") (pinfunction "PF7_25") (pintype "bidirectional"))
      (node (ref "X1") (pin "17") (pinfunction "1_17") (pintype "passive"))
    )
    (net (code "190") (name "SPI5_CSA") (class "Default")
      (node (ref "IC3") (pin "157") (pinfunction "PG14_157") (pintype "bidirectional"))
      (node (ref "X1") (pin "11") (pinfunction "1_11") (pintype "passive"))
    )
    (net (code "191") (name "SPI5_CSB") (class "Default")
      (node (ref "IC3") (pin "156") (pinfunction "PG13_156") (pintype "bidirectional"))
      (node (ref "X1") (pin "13") (pinfunction "1_13") (pintype "passive"))
    )
    (net (code "192") (name "SPI5_IRQ") (class "Default")
      (node (ref "IC3") (pin "138") (pinfunction "PA15_138") (pintype "bidirectional"))
      (node (ref "X1") (pin "9") (pinfunction "1_9") (pintype "passive"))
    )
    (net (code "193") (name "SPI5_MISO") (class "Default")
      (node (ref "IC3") (pin "26") (pinfunction "PF8_26") (pintype "bidirectional"))
      (node (ref "X1") (pin "18") (pinfunction "1_18") (pintype "passive"))
    )
    (net (code "194") (name "SPI5_MOSI") (class "Default")
      (node (ref "IC3") (pin "27") (pinfunction "PF9_27") (pintype "bidirectional"))
      (node (ref "X1") (pin "20") (pinfunction "1_20") (pintype "passive"))
    )
    (net (code "195") (name "SYS_JTCK-SWCLK") (class "Default")
      (node (ref "IC3") (pin "137") (pinfunction "PA14_137") (pintype "bidirectional"))
      (node (ref "R20") (pin "1") (pinfunction "1_1") (pintype "passive"))
    )
    (net (code "196") (name "SYS_JTDO-SWO") (class "Default")
      (node (ref "IC3") (pin "161") (pinfunction "PB3_161") (pintype "bidirectional"))
      (node (ref "IC5") (pin "5") (pinfunction "IO4_5") (pintype "bidirectional"))
      (node (ref "X4") (pin "6") (pinfunction "S_6") (pintype "passive"))
    )
    (net (code "197") (name "SYS_JTMS-SWDIO") (class "Default")
      (node (ref "IC3") (pin "128") (pinfunction "PA13_128") (pintype "bidirectional"))
      (node (ref "R19") (pin "1") (pinfunction "1_1") (pintype "passive"))
    )
    (net (code "198") (name "TCK") (class "Default")
      (node (ref "IC5") (pin "1") (pinfunction "IO1_1") (pintype "bidirectional"))
      (node (ref "R20") (pin "2") (pinfunction "2_2") (pintype "passive"))
      (node (ref "X4") (pin "2") (pinfunction "S_2") (pintype "passive"))
    )
    (net (code "199") (name "TFT_BRIGHTNESS") (class "Default")
      (node (ref "IC3") (pin "88") (pinfunction "PB15_88") (pintype "bidirectional"))
      (node (ref "IC9") (pin "4") (pinfunction "CTRL_4") (pintype "input"))
    )
    (net (code "200") (name "TMS") (class "Default")
      (node (ref "IC5") (pin "2") (pinfunction "IO2_2") (pintype "bidirectional"))
      (node (ref "R19") (pin "2") (pinfunction "2_2") (pintype "passive"))
      (node (ref "X4") (pin "4") (pinfunction "S_4") (pintype "passive"))
    )
    (net (code "201") (name "UART_RX{slash}DIN1") (class "Default")
      (node (ref "IC3") (pin "24") (pinfunction "PF6_24") (pintype "bidirectional"))
      (node (ref "R5") (pin "2") (pinfunction "2_2") (pintype "passive"))
      (node (ref "X1") (pin "3") (pinfunction "1_3") (pintype "passive"))
    )
    (net (code "202") (name "UART_TX{slash}DOUT1") (class "Default")
      (node (ref "IC2") (pin "11") (pinfunction "I_11") (pintype "input"))
      (node (ref "IC2") (pin "5") (pinfunction "I_5") (pintype "input"))
      (node (ref "IC3") (pin "162") (pinfunction "PB4_162") (pintype "bidirectional"))
      (node (ref "X1") (pin "4") (pinfunction "1_4") (pintype "passive"))
    )
    (net (code "203") (name "USB_D_N") (class "Default")
      (node (ref "IC10") (pin "1") (pinfunction "IO1_1") (pintype "bidirectional"))
      (node (ref "J2") (pin "2") (pinfunction "D-_2") (pintype "passive"))
      (node (ref "R28") (pin "1") (pinfunction "1_1") (pintype "passive"))
    )
    (net (code "204") (name "USB_D_P") (class "Default")
      (node (ref "IC10") (pin "2") (pinfunction "IO2_2") (pintype "bidirectional"))
      (node (ref "J2") (pin "3") (pinfunction "D+_3") (pintype "passive"))
      (node (ref "R29") (pin "1") (pinfunction "1_1") (pintype "passive"))
    )
    (net (code "205") (name "USB_OTG_FS_D_N") (class "Default")
      (node (ref "IC3") (pin "126") (pinfunction "PA11_126") (pintype "bidirectional"))
      (node (ref "R28") (pin "2") (pinfunction "2_2") (pintype "passive"))
    )
    (net (code "206") (name "USB_OTG_FS_D_P") (class "Default")
      (node (ref "IC3") (pin "127") (pinfunction "PA12_127") (pintype "bidirectional"))
      (node (ref "R29") (pin "2") (pinfunction "2_2") (pintype "passive"))
    )
    (net (code "207") (name "USB_OTG_FS_ID") (class "Default")
      (node (ref "IC10") (pin "4") (pinfunction "IO3_4") (pintype "bidirectional"))
      (node (ref "IC3") (pin "125") (pinfunction "PA10_125") (pintype "bidirectional"))
      (node (ref "J2") (pin "4") (pinfunction "ID_4") (pintype "passive"))
    )
    (net (code "208") (name "USB_OTG_FS_PSO") (class "Default")
      (node (ref "IC3") (pin "147") (pinfunction "PD5_147") (pintype "bidirectional"))
      (node (ref "IC8") (pin "4") (pinfunction "EN_4") (pintype "input"))
    )
    (net (code "209") (name "USB_OTG_FS_VBUS") (class "Default")
      (node (ref "C49") (pin "+") (pinfunction "+_+") (pintype "passive"))
      (node (ref "C52") (pin "2") (pinfunction "2_2") (pintype "passive"))
      (node (ref "IC10") (pin "6") (pinfunction "VCC_6") (pintype "passive"))
      (node (ref "IC3") (pin "124") (pinfunction "PA9_124") (pintype "bidirectional"))
      (node (ref "IC8") (pin "1") (pinfunction "OUT_1") (pintype "output"))
      (node (ref "J2") (pin "1") (pinfunction "VCC_1") (pintype "passive"))
      (node (ref "R27") (pin "1") (pinfunction "1_1") (pintype "passive"))
    )
    (net (code "210") (name "USER_SW") (class "Default")
      (node (ref "C4") (pin "2") (pinfunction "2_2") (pintype "passive"))
      (node (ref "IC3") (pin "152") (pinfunction "PG9_152") (pintype "bidirectional"))
      (node (ref "SW1") (pin "1") (pinfunction "1_1") (pintype "passive"))
    )
    (net (code "211") (name "VBAT") (class "Default")
      (node (ref "IC3") (pin "6") (pinfunction "VBAT_6") (pintype "power_in"))
      (node (ref "JP4") (pin "COM") (pinfunction "COM_COM") (pintype "passive"))
    )
    (net (code "212") (name "VCAP1") (class "Default")
      (node (ref "C37") (pin "1") (pinfunction "1_1") (pintype "passive"))
      (node (ref "IC3") (pin "81") (pinfunction "VCAP_1_81") (pintype "power_in"))
    )
    (net (code "213") (name "VCAP2") (class "Default")
      (node (ref "C36") (pin "1") (pinfunction "1_1") (pintype "passive"))
      (node (ref "IC3") (pin "129") (pinfunction "VCAP_2_129") (pintype "power_in"))
    )
    (net (code "214") (name "VDD") (class "Default")
      (node (ref "C16") (pin "1") (pinfunction "1_1") (pintype "passive"))
      (node (ref "C17") (pin "1") (pinfunction "1_1") (pintype "passive"))
      (node (ref "C18") (pin "1") (pinfunction "1_1") (pintype "passive"))
      (node (ref "C19") (pin "1") (pinfunction "1_1") (pintype "passive"))
      (node (ref "C20") (pin "1") (pinfunction "1_1") (pintype "passive"))
      (node (ref "C21") (pin "1") (pinfunction "1_1") (pintype "passive"))
      (node (ref "C22") (pin "+") (pinfunction "+_+") (pintype "passive"))
      (node (ref "C23") (pin "1") (pinfunction "1_1") (pintype "passive"))
      (node (ref "C24") (pin "1") (pinfunction "1_1") (pintype "passive"))
      (node (ref "C25") (pin "1") (pinfunction "1_1") (pintype "passive"))
      (node (ref "C26") (pin "1") (pinfunction "1_1") (pintype "passive"))
      (node (ref "C27") (pin "1") (pinfunction "1_1") (pintype "passive"))
      (node (ref "C28") (pin "1") (pinfunction "1_1") (pintype "passive"))
      (node (ref "C29") (pin "1") (pinfunction "1_1") (pintype "passive"))
      (node (ref "C30") (pin "1") (pinfunction "1_1") (pintype "passive"))
      (node (ref "C31") (pin "1") (pinfunction "1_1") (pintype "passive"))
      (node (ref "C32") (pin "1") (pinfunction "1_1") (pintype "passive"))
      (node (ref "C33") (pin "1") (pinfunction "1_1") (pintype "passive"))
      (node (ref "C8") (pin "2") (pinfunction "2_2") (pintype "passive"))
      (node (ref "FB1") (pin "P$1") (pinfunction "1_P$1") (pintype "passive"))
      (node (ref "IC3") (pin "118") (pinfunction "VDDUSB_118") (pintype "power_in"))
      (node (ref "IC3") (pin "131") (pinfunction "VDD_10_131") (pintype "power_in"))
      (node (ref "IC3") (pin "136") (pinfunction "VDD_11_136") (pintype "power_in"))
      (node (ref "IC3") (pin "149") (pinfunction "VDDSDMMC_149") (pintype "power_in"))
      (node (ref "IC3") (pin "15") (pinfunction "VDD_2_15") (pintype "power_in"))
      (node (ref "IC3") (pin "159") (pinfunction "VDD_12_159") (pintype "power_in"))
      (node (ref "IC3") (pin "171") (pinfunction "PDR_ON_171") (pintype "passive"))
      (node (ref "IC3") (pin "172") (pinfunction "VDD_172") (pintype "power_in"))
      (node (ref "IC3") (pin "23") (pinfunction "VDD_3_23") (pintype "power_in"))
      (node (ref "IC3") (pin "36") (pinfunction "VDD_4_36") (pintype "power_in"))
      (node (ref "IC3") (pin "49") (pinfunction "VDD_5_49") (pintype "power_in"))
      (node (ref "IC3") (pin "62") (pinfunction "VDD_6_62") (pintype "power_in"))
      (node (ref "IC3") (pin "72") (pinfunction "VDD_7_72") (pintype "power_in"))
      (node (ref "IC3") (pin "82") (pinfunction "VDD_8_82") (pintype "power_in"))
      (node (ref "IC3") (pin "96") (pinfunction "VDD_9_96") (pintype "power_in"))
      (node (ref "IC3") (pin "99") (pinfunction "VDDDSI_99") (pintype "power_in"))
      (node (ref "JP2") (pin "1") (pinfunction "1_1") (pintype "passive"))
      (node (ref "JP4") (pin "NO") (pinfunction "NO_NO") (pintype "passive"))
      (node (ref "R11") (pin "1") (pinfunction "1_1") (pintype "passive"))
    )
    (net (code "215") (name "VDDA") (class "Default")
      (node (ref "C34") (pin "1") (pinfunction "1_1") (pintype "passive"))
      (node (ref "C35") (pin "1") (pinfunction "1_1") (pintype "passive"))
      (node (ref "FB1") (pin "P$2") (pinfunction "2_P$2") (pintype "passive"))
      (node (ref "IC3") (pin "39") (pinfunction "VDDA_39") (pintype "power_in"))
      (node (ref "R17") (pin "2") (pinfunction "2_2") (pintype "passive"))
    )
    (net (code "216") (name "VLED+") (class "Default")
      (node (ref "C48") (pin "1") (pinfunction "1_1") (pintype "passive"))
      (node (ref "D2") (pin "C") (pinfunction "C_C") (pintype "passive"))
      (node (ref "LCD1") (pin "2") (pinfunction "VLED+_2") (pintype "power_in"))
      (node (ref "ZD1") (pin "C") (pinfunction "C_C") (pintype "passive"))
    )
    (net (code "217") (name "VLED-") (class "Default")
      (node (ref "IC9") (pin "3") (pinfunction "FB_3") (pintype "input"))
      (node (ref "LCD1") (pin "1") (pinfunction "VLED-_1") (pintype "power_in"))
      (node (ref "R25") (pin "1") (pinfunction "1_1") (pintype "passive"))
      (node (ref "ZD1") (pin "A") (pinfunction "A_A") (pintype "passive"))
    )
    (net (code "218") (name "VREF+") (class "Default")
      (node (ref "IC3") (pin "38") (pinfunction "VREF+_38") (pintype "power_in"))
      (node (ref "R17") (pin "1") (pinfunction "1_1") (pintype "passive"))
    )
    (net (code "219") (name "XL") (class "Default")
      (node (ref "IC11") (pin "4") (pinfunction "IO3_4") (pintype "bidirectional"))
      (node (ref "IC12") (pin "4") (pinfunction "X-_4") (pintype "input"))
      (node (ref "LCD1") (pin "39") (pinfunction "XL_39") (pintype "passive"))
    )
    (net (code "220") (name "XR") (class "Default")
      (node (ref "IC11") (pin "1") (pinfunction "IO1_1") (pintype "bidirectional"))
      (node (ref "IC12") (pin "2") (pinfunction "X+_2") (pintype "input"))
      (node (ref "LCD1") (pin "37") (pinfunction "XR_37") (pintype "passive"))
    )
    (net (code "221") (name "YD") (class "Default")
      (node (ref "IC11") (pin "2") (pinfunction "IO2_2") (pintype "bidirectional"))
      (node (ref "IC12") (pin "5") (pinfunction "Y-_5") (pintype "input"))
      (node (ref "LCD1") (pin "38") (pinfunction "YD_38") (pintype "passive"))
    )
    (net (code "222") (name "YU") (class "Default")
      (node (ref "IC11") (pin "5") (pinfunction "IO4_5") (pintype "bidirectional"))
      (node (ref "IC12") (pin "3") (pinfunction "Y+_3") (pintype "input"))
      (node (ref "LCD1") (pin "40") (pinfunction "YU_40") (pintype "passive"))
    )
    (net (code "223") (name "unconnected-(IC3A-PC10-Pad139)") (class "Default")
      (node (ref "IC3") (pin "139") (pinfunction "PC10_139") (pintype "bidirectional"))
    )
    (net (code "224") (name "unconnected-(IC3A-PD6-Pad150)") (class "Default")
      (node (ref "IC3") (pin "150") (pinfunction "PD6_150") (pintype "bidirectional"))
    )
    (net (code "225") (name "unconnected-(IC3C-DSI_CKN-Pad105)") (class "Default")
      (node (ref "IC3") (pin "105") (pinfunction "DSI_CKN_105") (pintype "bidirectional"))
    )
    (net (code "226") (name "unconnected-(IC3C-DSI_CKP-Pad104)") (class "Default")
      (node (ref "IC3") (pin "104") (pinfunction "DSI_CKP_104") (pintype "bidirectional"))
    )
    (net (code "227") (name "unconnected-(IC3C-DSI_D0N-Pad102)") (class "Default")
      (node (ref "IC3") (pin "102") (pinfunction "DSI_D0N_102") (pintype "bidirectional"))
    )
    (net (code "228") (name "unconnected-(IC3C-DSI_D0P-Pad101)") (class "Default")
      (node (ref "IC3") (pin "101") (pinfunction "DSI_D0P_101") (pintype "bidirectional"))
    )
    (net (code "229") (name "unconnected-(IC3C-DSI_D1N-Pad108)") (class "Default")
      (node (ref "IC3") (pin "108") (pinfunction "DSI_D1N_108") (pintype "bidirectional"))
    )
    (net (code "230") (name "unconnected-(IC3C-DSI_D1P-Pad107)") (class "Default")
      (node (ref "IC3") (pin "107") (pinfunction "DSI_D1P_107") (pintype "bidirectional"))
    )
    (net (code "231") (name "unconnected-(IC3C-PI8-Pad7)") (class "Default")
      (node (ref "IC3") (pin "7") (pinfunction "PI8_7") (pintype "bidirectional"))
    )
    (net (code "232") (name "unconnected-(IC6-A12{slash}NC-36-Pad36)") (class "Default")
      (node (ref "IC6") (pin "36") (pinfunction "A12/NC-36_36") (pintype "passive"))
    )
    (net (code "233") (name "unconnected-(IC6-NC-40-Pad40)") (class "Default")
      (node (ref "IC6") (pin "40") (pinfunction "NC-40_40") (pintype "no_connect"))
    )
    (net (code "234") (name "unconnected-(IC10-IO4-Pad5)") (class "Default")
      (node (ref "IC10") (pin "5") (pinfunction "IO4_5") (pintype "bidirectional"))
    )
    (net (code "235") (name "unconnected-(IC12-AUX-Pad16)") (class "Default")
      (node (ref "IC12") (pin "16") (pinfunction "AUX_16") (pintype "input"))
    )
    (net (code "236") (name "unconnected-(IC14-CLK_OUT-Pad25)") (class "Default")
      (node (ref "IC14") (pin "25") (pinfunction "CLK_OUT_25") (pintype "output"))
    )
    (net (code "237") (name "unconnected-(IC14-TCK-Pad8)") (class "Default")
      (node (ref "IC14") (pin "8") (pinfunction "TCK_8") (pintype "input"))
    )
    (net (code "238") (name "unconnected-(IC14-TDI-Pad12)") (class "Default")
      (node (ref "IC14") (pin "12") (pinfunction "TDI_12") (pintype "input"))
    )
    (net (code "239") (name "unconnected-(IC14-TDO-Pad9)") (class "Default")
      (node (ref "IC14") (pin "9") (pinfunction "TDO_9") (pintype "output"))
    )
    (net (code "240") (name "unconnected-(IC14-TMS-Pad10)") (class "Default")
      (node (ref "IC14") (pin "10") (pinfunction "TMS_10") (pintype "input"))
    )
    (net (code "241") (name "unconnected-(IC14-X2-Pad33)") (class "Default")
      (node (ref "IC14") (pin "33") (pinfunction "X2_33") (pintype "output"))
    )
    (net (code "242") (name "unconnected-(IC14-~{TRST}-Pad11)") (class "Default")
      (node (ref "IC14") (pin "11") (pinfunction "~{TRST}_11") (pintype "input"))
    )
    (net (code "243") (name "unconnected-(J1-CD{slash}DAT3-Pad2)") (class "Default")
      (node (ref "J1") (pin "2") (pinfunction "CD/DAT3_2") (pintype "passive"))
    )
    (net (code "244") (name "unconnected-(J1-DAT1-Pad8)") (class "Default")
      (node (ref "J1") (pin "8") (pinfunction "DAT1_8") (pintype "passive"))
    )
    (net (code "245") (name "unconnected-(J1-DAT2-Pad1)") (class "Default")
      (node (ref "J1") (pin "1") (pinfunction "DAT2_1") (pintype "passive"))
    )
    (net (code "246") (name "unconnected-(LCD1-NC1-Pad35)") (class "Default")
      (node (ref "LCD1") (pin "35") (pinfunction "NC1_35") (pintype "no_connect"))
    )
    (net (code "247") (name "~{FAULT}") (class "Default")
      (node (ref "IC3") (pin "58") (pinfunction "PB2_58") (pintype "bidirectional"))
      (node (ref "R14") (pin "2") (pinfunction "2_2") (pintype "passive"))
      (node (ref "X1") (pin "8") (pinfunction "1_8") (pintype "passive"))
      (node (ref "X2") (pin "15") (pinfunction "1_15") (pintype "passive"))
    )
    (net (code "248") (name "~{RESET}") (class "Default")
      (node (ref "C8") (pin "1") (pinfunction "1_1") (pintype "passive"))
      (node (ref "IC14") (pin "29") (pinfunction "RESET_N_29") (pintype "input"))
      (node (ref "IC3") (pin "31") (pinfunction "NRST_31") (pintype "bidirectional"))
      (node (ref "IC5") (pin "4") (pinfunction "IO3_4") (pintype "bidirectional"))
      (node (ref "JP7") (pin "NO") (pinfunction "NO_NO") (pintype "passive"))
      (node (ref "R11") (pin "2") (pinfunction "2_2") (pintype "passive"))
      (node (ref "X1") (pin "6") (pinfunction "1_6") (pintype "passive"))
      (node (ref "X4") (pin "5") (pinfunction "S_5") (pintype "passive"))
    )
    (net (code "249") (name "~{USB_OTG_FS_OC}") (class "Default")
      (node (ref "IC3") (pin "146") (pinfunction "PD4_146") (pintype "bidirectional"))
      (node (ref "IC8") (pin "3") (pinfunction "~{OC}_3") (pintype "passive"))
      (node (ref "R26") (pin "1") (pinfunction "1_1") (pintype "passive"))
    )
  )
)
